# STM32F767ZI_eval_1.net
KiCad netlist of a schematic drawn in EAGLE
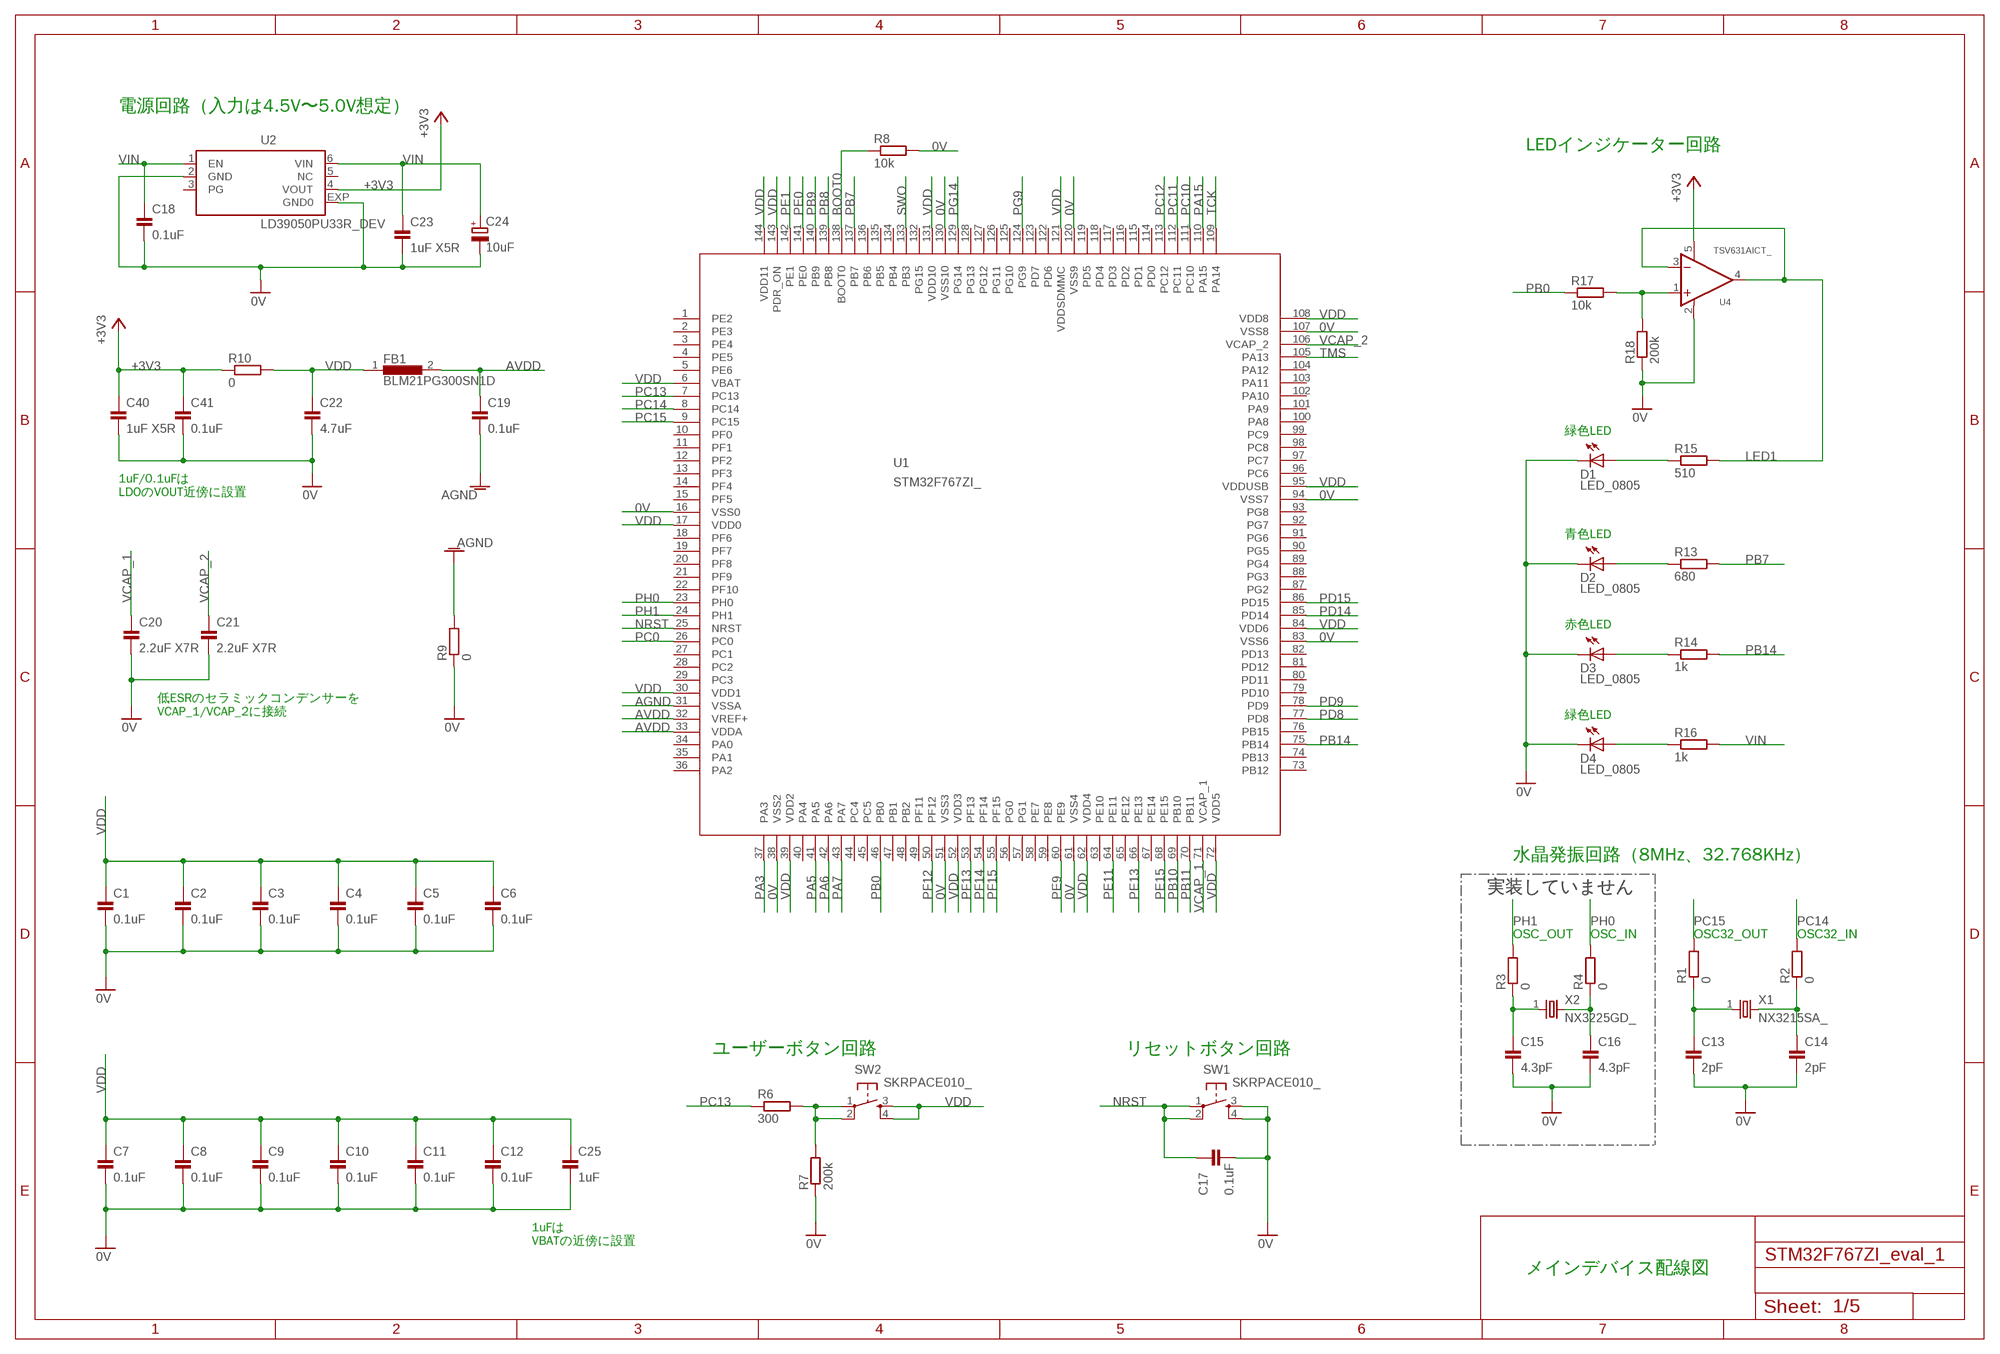
[diagram p0: schematic, sheet 1]
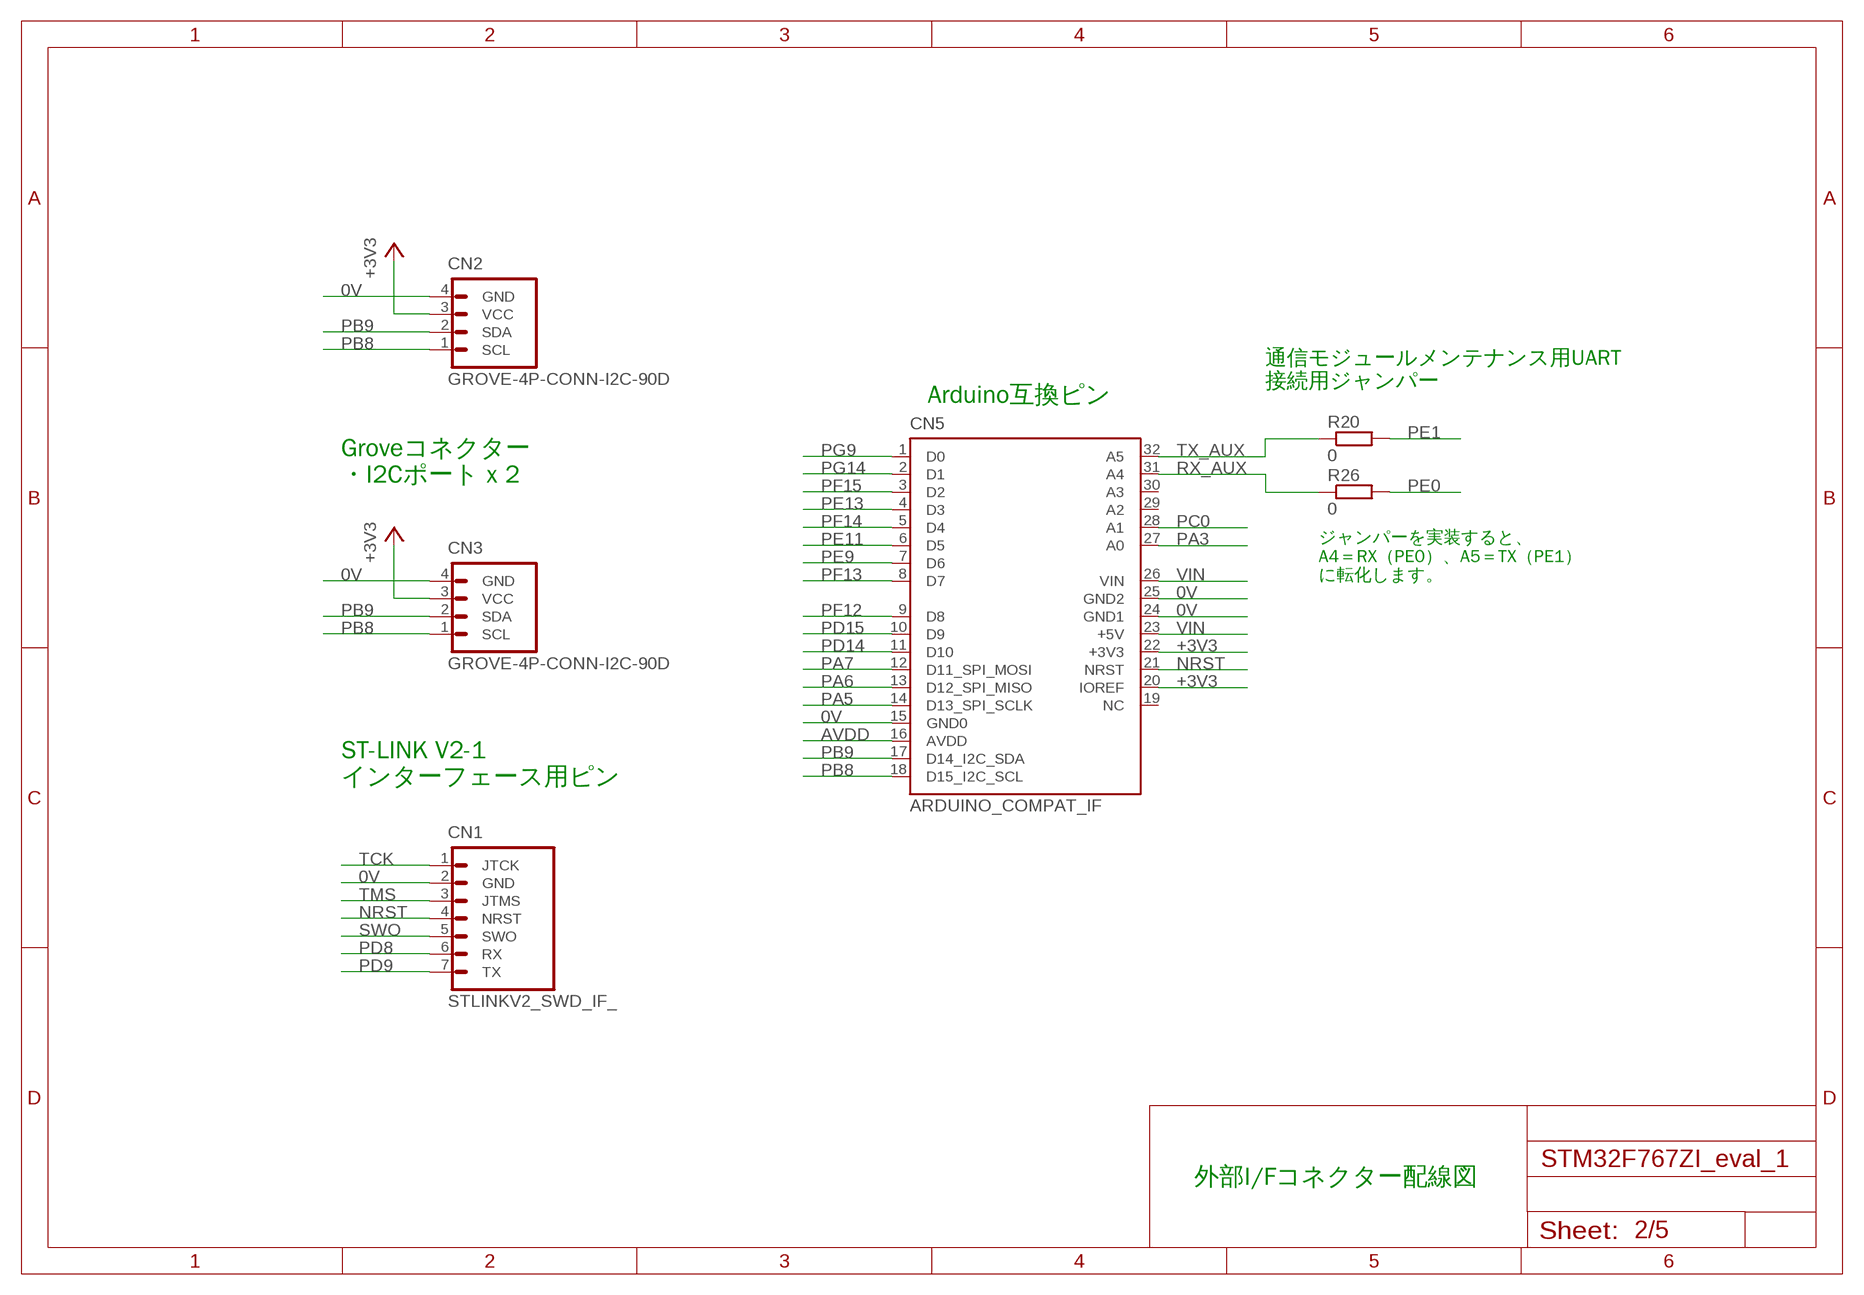
[diagram p1: schematic, sheet 2]
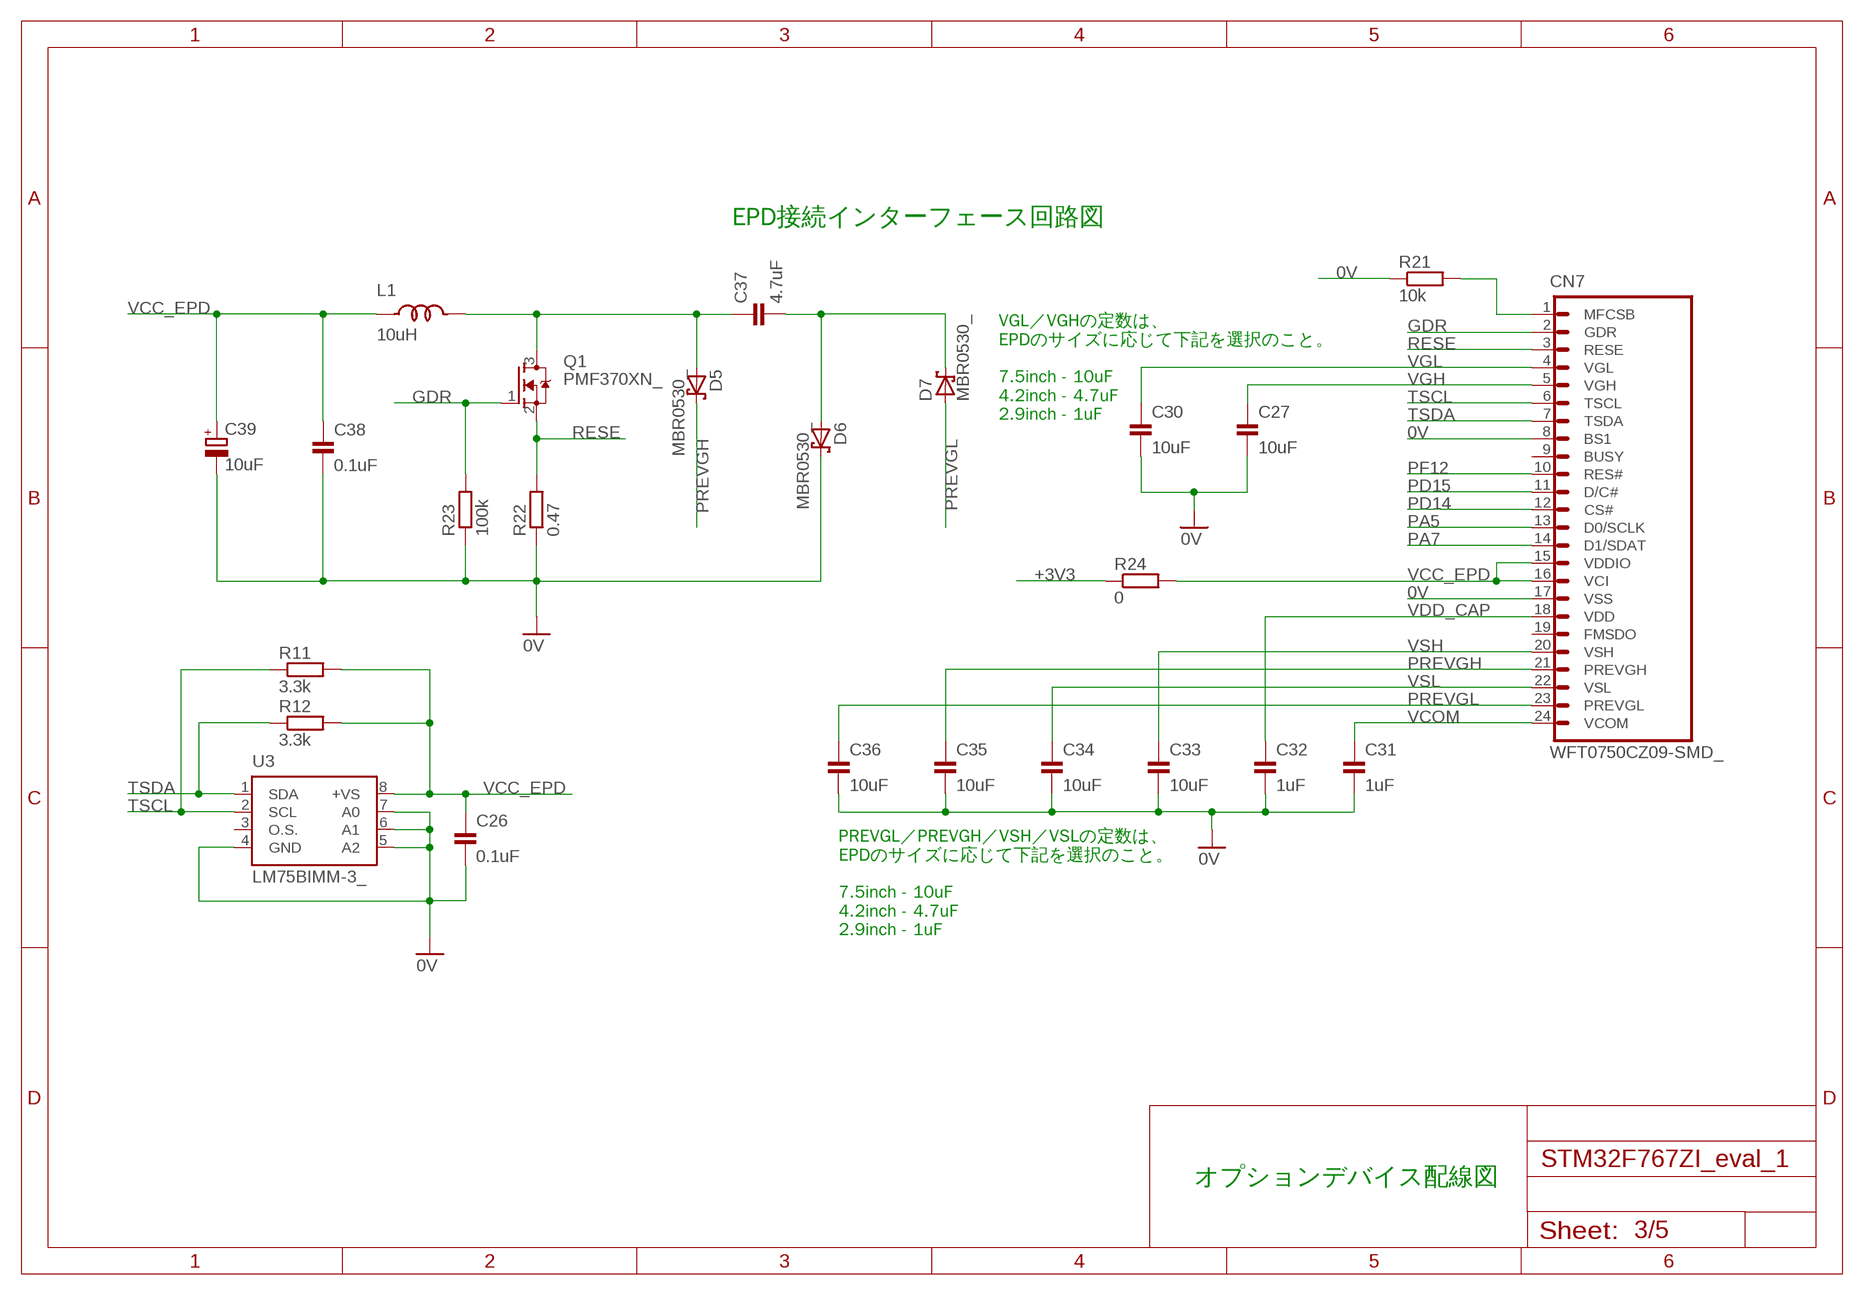
[diagram p2: schematic, sheet 3]
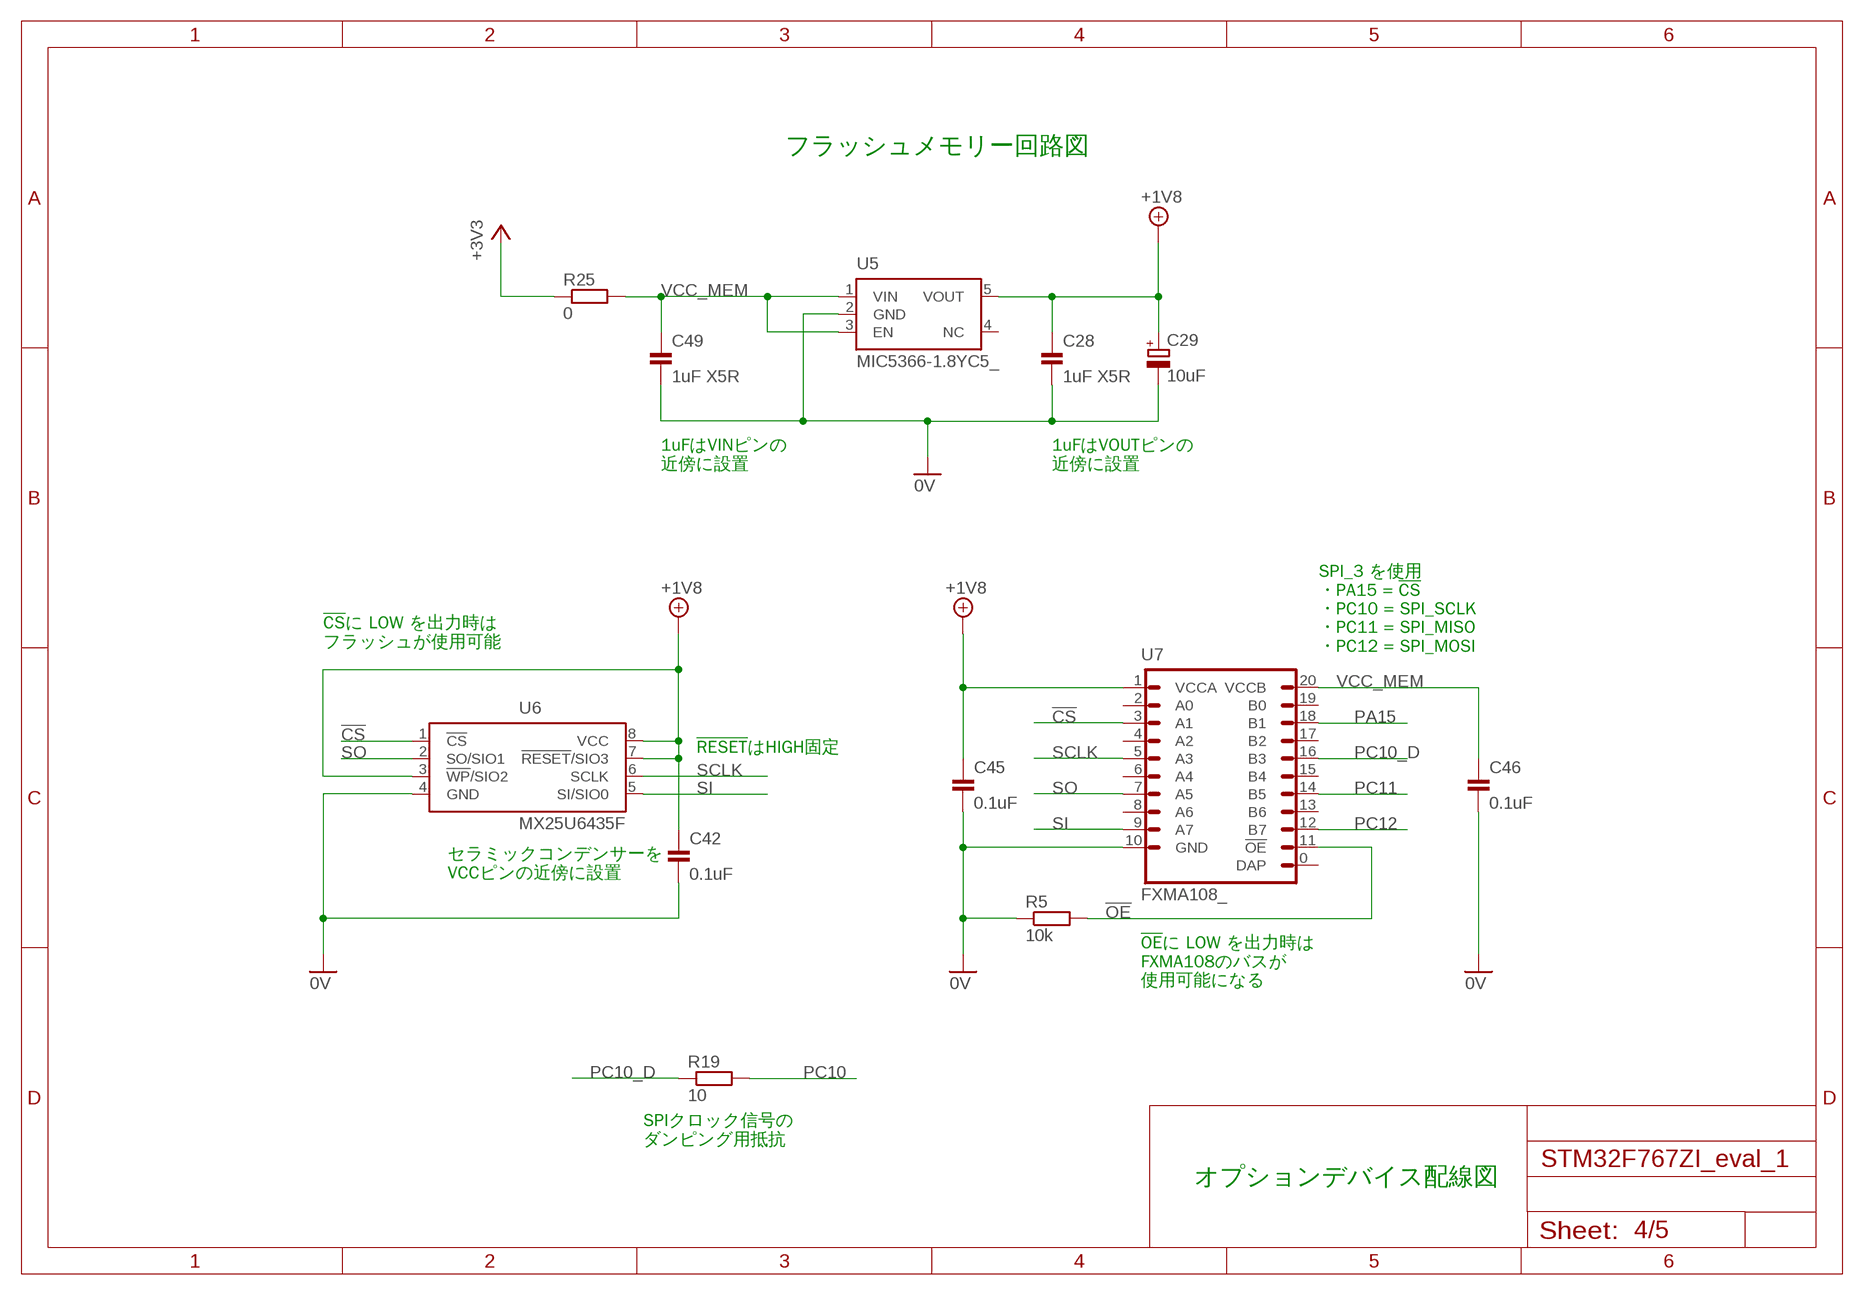
[diagram p3: schematic, sheet 4]
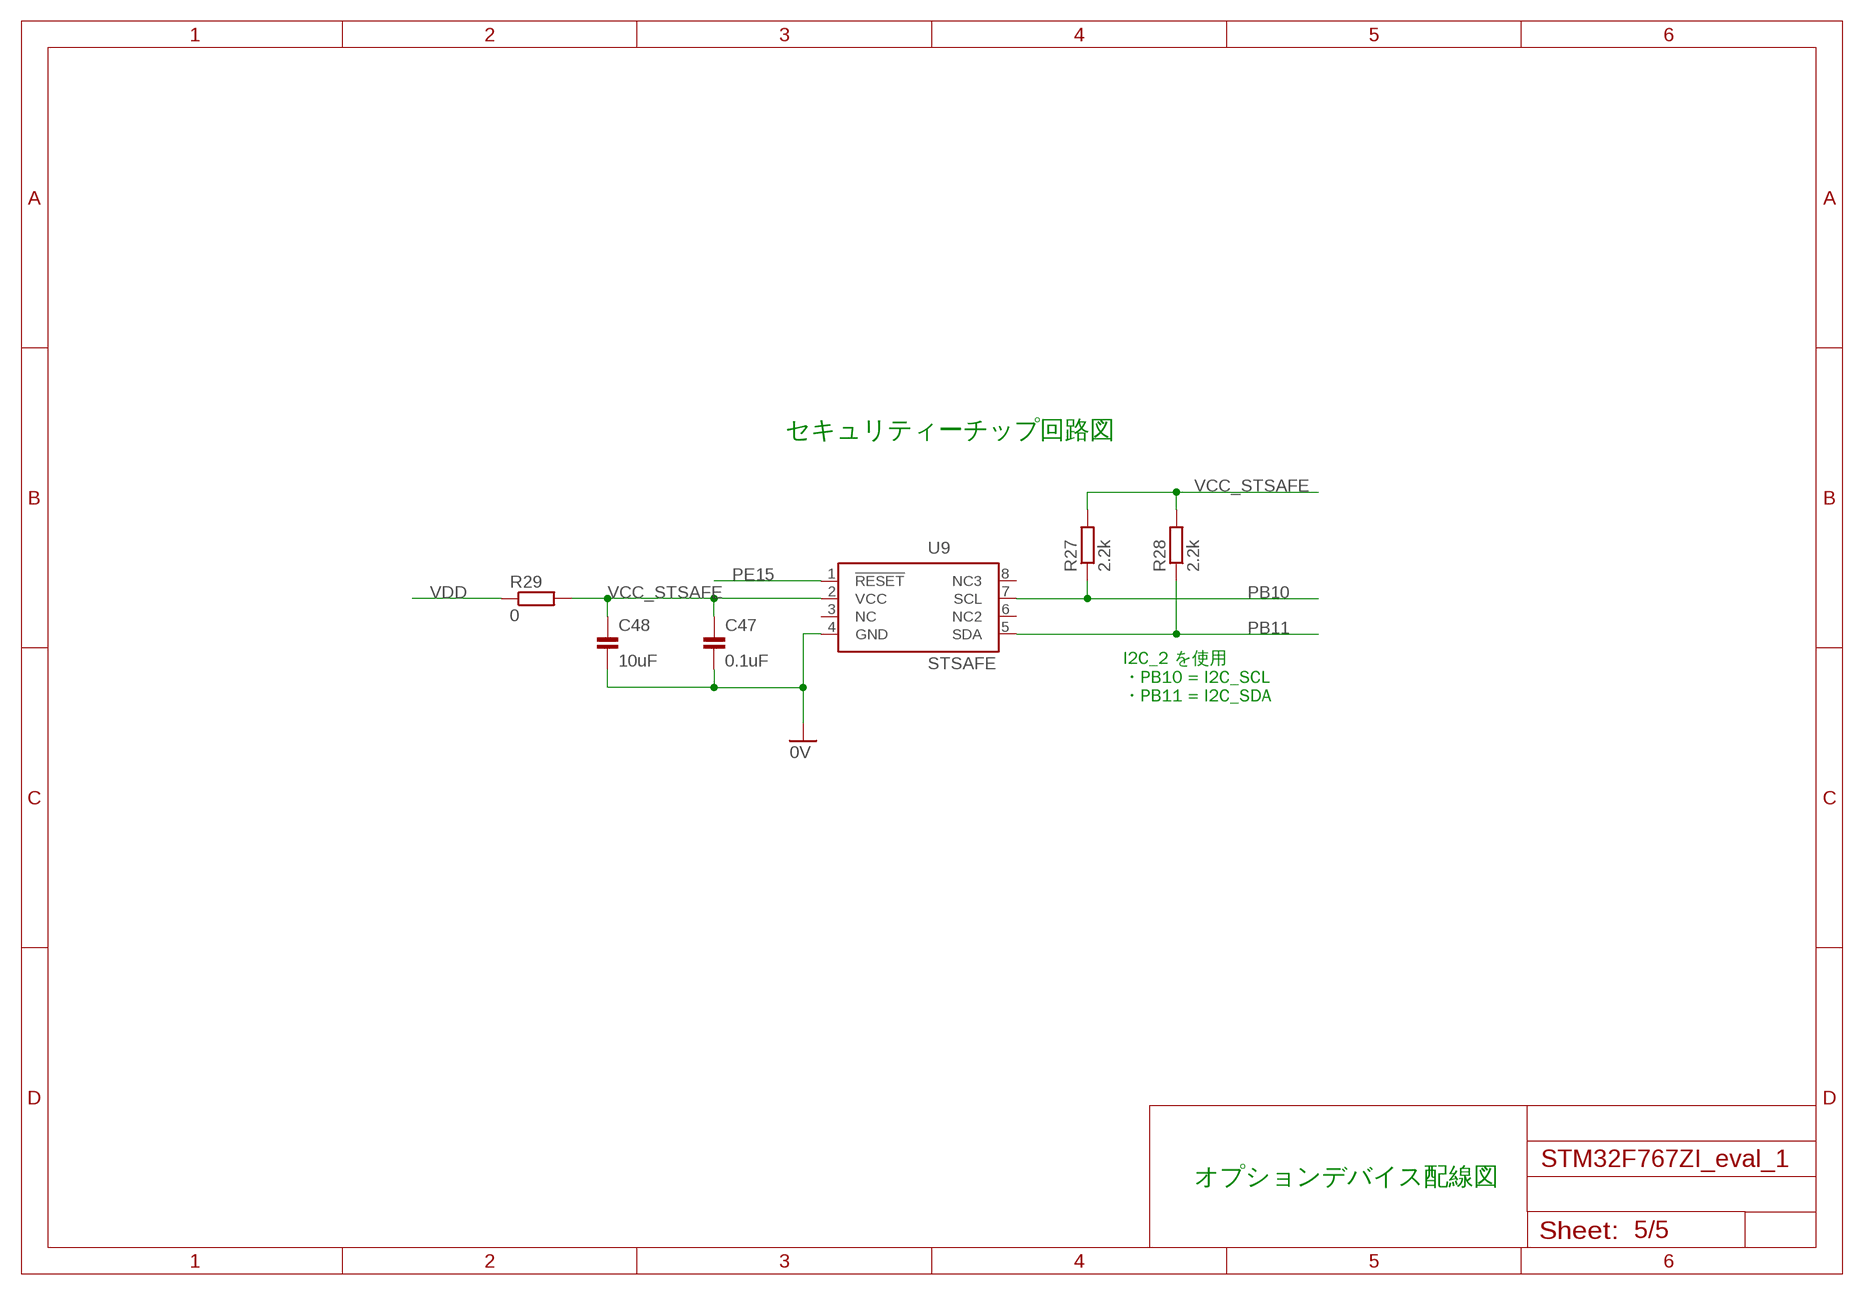
[diagram p4: schematic, sheet 5]

(export (version "E")
  (design (tool "Eeschema 10.0.6"))
  (components
    (comp (ref "C1")
      (value "0.1uF")
      (footprint "eagle-import:SMD_1608_DEV")
      (libsource (lib "eagle-import") (part "CAP_0603_DEV"))
    )
    (comp (ref "C2")
      (value "0.1uF")
      (footprint "eagle-import:SMD_1608_DEV")
      (libsource (lib "eagle-import") (part "CAP_0603_DEV"))
    )
    (comp (ref "C3")
      (value "0.1uF")
      (footprint "eagle-import:SMD_1608_DEV")
      (libsource (lib "eagle-import") (part "CAP_0603_DEV"))
    )
    (comp (ref "C4")
      (value "0.1uF")
      (footprint "eagle-import:SMD_1608_DEV")
      (libsource (lib "eagle-import") (part "CAP_0603_DEV"))
    )
    (comp (ref "C5")
      (value "0.1uF")
      (footprint "eagle-import:SMD_1608_DEV")
      (libsource (lib "eagle-import") (part "CAP_0603_DEV"))
    )
    (comp (ref "C6")
      (value "0.1uF")
      (footprint "eagle-import:SMD_1608_DEV")
      (libsource (lib "eagle-import") (part "CAP_0603_DEV"))
    )
    (comp (ref "C7")
      (value "0.1uF")
      (footprint "eagle-import:SMD_1608_DEV")
      (libsource (lib "eagle-import") (part "CAP_0603_DEV"))
    )
    (comp (ref "C8")
      (value "0.1uF")
      (footprint "eagle-import:SMD_1608_DEV")
      (libsource (lib "eagle-import") (part "CAP_0603_DEV"))
    )
    (comp (ref "C9")
      (value "0.1uF")
      (footprint "eagle-import:SMD_1608_DEV")
      (libsource (lib "eagle-import") (part "CAP_0603_DEV"))
    )
    (comp (ref "C10")
      (value "0.1uF")
      (footprint "eagle-import:SMD_1608_DEV")
      (libsource (lib "eagle-import") (part "CAP_0603_DEV"))
    )
    (comp (ref "C11")
      (value "0.1uF")
      (footprint "eagle-import:SMD_1608_DEV")
      (libsource (lib "eagle-import") (part "CAP_0603_DEV"))
    )
    (comp (ref "C12")
      (value "0.1uF")
      (footprint "eagle-import:SMD_1608_DEV")
      (libsource (lib "eagle-import") (part "CAP_0603_DEV"))
    )
    (comp (ref "C13")
      (value "2pF")
      (footprint "eagle-import:SMD_1608_DEV")
      (libsource (lib "eagle-import") (part "CAP_0603_DEV"))
    )
    (comp (ref "C14")
      (value "2pF")
      (footprint "eagle-import:SMD_1608_DEV")
      (libsource (lib "eagle-import") (part "CAP_0603_DEV"))
    )
    (comp (ref "C15")
      (value "4.3pF")
      (footprint "eagle-import:SMD_1608_DEV")
      (libsource (lib "eagle-import") (part "CAP_0603_DEV"))
    )
    (comp (ref "C16")
      (value "4.3pF")
      (footprint "eagle-import:SMD_1608_DEV")
      (libsource (lib "eagle-import") (part "CAP_0603_DEV"))
    )
    (comp (ref "C17")
      (value "0.1uF")
      (footprint "eagle-import:SMD_1608_DEV")
      (libsource (lib "eagle-import") (part "CAP_0603_DEV"))
    )
    (comp (ref "C18")
      (value "0.1uF")
      (footprint "eagle-import:SMD_1608_DEV")
      (libsource (lib "eagle-import") (part "CAP_0603_DEV"))
    )
    (comp (ref "C19")
      (value "0.1uF")
      (footprint "eagle-import:SMD_1608_DEV")
      (libsource (lib "eagle-import") (part "CAP_0603_DEV"))
    )
    (comp (ref "C20")
      (value "2.2uF X7R")
      (footprint "eagle-import:C1206")
      (libsource (lib "eagle-import") (part "CAP_1206"))
    )
    (comp (ref "C21")
      (value "2.2uF X7R")
      (footprint "eagle-import:C1206")
      (libsource (lib "eagle-import") (part "CAP_1206"))
    )
    (comp (ref "C22")
      (value "4.7uF")
      (footprint "eagle-import:SMD_2012_DEV")
      (libsource (lib "eagle-import") (part "CAP_0805_DEV"))
    )
    (comp (ref "C23")
      (value "1uF X5R")
      (footprint "eagle-import:SMD_1608_DEV")
      (libsource (lib "eagle-import") (part "CAP_0603_DEV"))
    )
    (comp (ref "C24")
      (value "10uF")
      (footprint "eagle-import:C1210_TPST_DEV")
      (libsource (lib "eagle-import") (part "TPST106K016R0800_"))
    )
    (comp (ref "C25")
      (value "1uF")
      (footprint "eagle-import:SMD_1608_DEV")
      (libsource (lib "eagle-import") (part "CAP_0603_DEV"))
    )
    (comp (ref "C40")
      (value "1uF X5R")
      (footprint "eagle-import:SMD_1608_DEV")
      (libsource (lib "eagle-import") (part "CAP_0603_DEV"))
    )
    (comp (ref "C41")
      (value "0.1uF")
      (footprint "eagle-import:SMD_1608_DEV")
      (libsource (lib "eagle-import") (part "CAP_0603_DEV"))
    )
    (comp (ref "D1")
      (value "LED_0805")
      (footprint "eagle-import:CHIPLED_0805")
      (libsource (lib "eagle-import") (part "LED_0805"))
    )
    (comp (ref "D2")
      (value "LED_0805")
      (footprint "eagle-import:CHIPLED_0805")
      (libsource (lib "eagle-import") (part "LED_0805"))
    )
    (comp (ref "D3")
      (value "LED_0805")
      (footprint "eagle-import:CHIPLED_0805")
      (libsource (lib "eagle-import") (part "LED_0805"))
    )
    (comp (ref "D4")
      (value "LED_0805")
      (footprint "eagle-import:CHIPLED_0805")
      (libsource (lib "eagle-import") (part "LED_0805"))
    )
    (comp (ref "FB1")
      (value "BLM21PG300SN1D")
      (footprint "eagle-import:SMD_2012_DEV")
      (libsource (lib "eagle-import") (part "BLM21PG300SN1D"))
    )
    (comp (ref "R1")
      (value "0")
      (footprint "eagle-import:SMD_1608_DEV")
      (libsource (lib "eagle-import") (part "RESISTOR_0603_DEV"))
    )
    (comp (ref "R2")
      (value "0")
      (footprint "eagle-import:SMD_1608_DEV")
      (libsource (lib "eagle-import") (part "RESISTOR_0603_DEV"))
    )
    (comp (ref "R3")
      (value "0")
      (footprint "eagle-import:SMD_1608_DEV")
      (libsource (lib "eagle-import") (part "RESISTOR_0603_DEV"))
    )
    (comp (ref "R4")
      (value "0")
      (footprint "eagle-import:SMD_1608_DEV")
      (libsource (lib "eagle-import") (part "RESISTOR_0603_DEV"))
    )
    (comp (ref "R6")
      (value "300")
      (footprint "eagle-import:SMD_1608_DEV")
      (libsource (lib "eagle-import") (part "RESISTOR_0603_DEV"))
    )
    (comp (ref "R7")
      (value "200k")
      (footprint "eagle-import:SMD_1608_DEV")
      (libsource (lib "eagle-import") (part "RESISTOR_0603_DEV"))
    )
    (comp (ref "R8")
      (value "10k")
      (footprint "eagle-import:SMD_1608_DEV")
      (libsource (lib "eagle-import") (part "RESISTOR_0603_DEV"))
    )
    (comp (ref "R9")
      (value "0")
      (footprint "eagle-import:SMD_1608_DEV")
      (libsource (lib "eagle-import") (part "RESISTOR_0603_DEV"))
    )
    (comp (ref "R10")
      (value "0")
      (footprint "eagle-import:SMD_1608_DEV")
      (libsource (lib "eagle-import") (part "RESISTOR_0603_DEV"))
    )
    (comp (ref "R13")
      (value "680")
      (footprint "eagle-import:SMD_1608_DEV")
      (libsource (lib "eagle-import") (part "RESISTOR_0603_DEV"))
    )
    (comp (ref "R14")
      (value "1k")
      (footprint "eagle-import:SMD_1608_DEV")
      (libsource (lib "eagle-import") (part "RESISTOR_0603_DEV"))
    )
    (comp (ref "R15")
      (value "510")
      (footprint "eagle-import:SMD_1608_DEV")
      (libsource (lib "eagle-import") (part "RESISTOR_0603_DEV"))
    )
    (comp (ref "R16")
      (value "1k")
      (footprint "eagle-import:SMD_1608_DEV")
      (libsource (lib "eagle-import") (part "RESISTOR_0603_DEV"))
    )
    (comp (ref "R17")
      (value "10k")
      (footprint "eagle-import:SMD_1608_DEV")
      (libsource (lib "eagle-import") (part "RESISTOR_0603_DEV"))
    )
    (comp (ref "R18")
      (value "200k")
      (footprint "eagle-import:SMD_1608_DEV")
      (libsource (lib "eagle-import") (part "RESISTOR_0603_DEV"))
    )
    (comp (ref "SW1")
      (value "SKRPACE010_")
      (footprint "eagle-import:SKRPACE010_DEV")
      (libsource (lib "eagle-import") (part "SKRPACE010_"))
    )
    (comp (ref "SW2")
      (value "SKRPACE010_")
      (footprint "eagle-import:SKRPACE010_DEV")
      (libsource (lib "eagle-import") (part "SKRPACE010_"))
    )
    (comp (ref "U1")
      (value "STM32F767ZI_")
      (footprint "eagle-import:LQFP144_DEV")
      (libsource (lib "eagle-import") (part "STM32F767ZI_"))
    )
    (comp (ref "U2")
      (value "LD39050PU33R_DEV")
      (footprint "eagle-import:DFN6-3X3_")
      (libsource (lib "eagle-import") (part "LD39050PU33R_DEV"))
    )
    (comp (ref "U4")
      (value "TSV631AICT_")
      (footprint "eagle-import:SC-70-5_DEV")
      (libsource (lib "eagle-import") (part "TSV631AICT_"))
    )
    (comp (ref "X1")
      (value "NX3215SA_")
      (footprint "eagle-import:NX3215_DEV")
      (libsource (lib "eagle-import") (part "NX3215SA_"))
    )
    (comp (ref "X2")
      (value "NX3225GD_")
      (footprint "eagle-import:NX3225_DEV")
      (libsource (lib "eagle-import") (part "NX3225GD_"))
    )
    (comp (ref "C47")
      (value "0.1uF")
      (footprint "eagle-import:SMD_1608_DEV")
      (libsource (lib "eagle-import") (part "CAP_0603_DEV"))
    )
    (comp (ref "C48")
      (value "10uF")
      (footprint "eagle-import:SMD_2012_DEV")
      (libsource (lib "eagle-import") (part "CAP_0805_DEV"))
    )
    (comp (ref "R27")
      (value "2.2k")
      (footprint "eagle-import:SMD_1608_DEV")
      (libsource (lib "eagle-import") (part "RESISTOR_0603_DEV"))
    )
    (comp (ref "R28")
      (value "2.2k")
      (footprint "eagle-import:SMD_1608_DEV")
      (libsource (lib "eagle-import") (part "RESISTOR_0603_DEV"))
    )
    (comp (ref "R29")
      (value "0")
      (footprint "eagle-import:SMD_1608_DEV")
      (libsource (lib "eagle-import") (part "RESISTOR_0603_DEV"))
    )
    (comp (ref "U9")
      (value "STSAFE")
      (footprint "eagle-import:SO8N")
      (libsource (lib "eagle-import") (part "STSAFE"))
    )
    (comp (ref "C26")
      (value "0.1uF")
      (footprint "eagle-import:SMD_1608_DEV")
      (libsource (lib "eagle-import") (part "CAP_0603_DEV"))
    )
    (comp (ref "C27")
      (value "10uF")
      (footprint "eagle-import:SMD_2012_DEV")
      (libsource (lib "eagle-import") (part "CAP_0805_DEV"))
    )
    (comp (ref "C30")
      (value "10uF")
      (footprint "eagle-import:SMD_2012_DEV")
      (libsource (lib "eagle-import") (part "CAP_0805_DEV"))
    )
    (comp (ref "C31")
      (value "1uF")
      (footprint "eagle-import:SMD_2012_DEV")
      (libsource (lib "eagle-import") (part "CAP_0805_DEV"))
    )
    (comp (ref "C32")
      (value "1uF")
      (footprint "eagle-import:SMD_2012_DEV")
      (libsource (lib "eagle-import") (part "CAP_0805_DEV"))
    )
    (comp (ref "C33")
      (value "10uF")
      (footprint "eagle-import:SMD_2012_DEV")
      (libsource (lib "eagle-import") (part "CAP_0805_DEV"))
    )
    (comp (ref "C34")
      (value "10uF")
      (footprint "eagle-import:SMD_2012_DEV")
      (libsource (lib "eagle-import") (part "CAP_0805_DEV"))
    )
    (comp (ref "C35")
      (value "10uF")
      (footprint "eagle-import:SMD_2012_DEV")
      (libsource (lib "eagle-import") (part "CAP_0805_DEV"))
    )
    (comp (ref "C36")
      (value "10uF")
      (footprint "eagle-import:SMD_2012_DEV")
      (libsource (lib "eagle-import") (part "CAP_0805_DEV"))
    )
    (comp (ref "C37")
      (value "4.7uF")
      (footprint "eagle-import:SMD_2012_DEV")
      (libsource (lib "eagle-import") (part "CAP_0805_DEV"))
    )
    (comp (ref "C38")
      (value "0.1uF")
      (footprint "eagle-import:SMD_1608_DEV")
      (libsource (lib "eagle-import") (part "CAP_0603_DEV"))
    )
    (comp (ref "C39")
      (value "10uF")
      (footprint "eagle-import:C1210_TPST_DEV")
      (libsource (lib "eagle-import") (part "TPST106K016R0800_"))
    )
    (comp (ref "CN7")
      (value "WFT0750CZ09-SMD_")
      (footprint "eagle-import:FH12A-24S-0.5SH_DEV")
      (libsource (lib "eagle-import") (part "WFT0750CZ09-SMD_"))
    )
    (comp (ref "D5")
      (value "MBR0530_")
      (footprint "eagle-import:MBR0530_DEV")
      (libsource (lib "eagle-import") (part "MBR0530_"))
    )
    (comp (ref "D6")
      (value "MBR0530_")
      (footprint "eagle-import:MBR0530_DEV")
      (libsource (lib "eagle-import") (part "MBR0530_"))
    )
    (comp (ref "D7")
      (value "MBR0530_")
      (footprint "eagle-import:MBR0530_DEV")
      (libsource (lib "eagle-import") (part "MBR0530_"))
    )
    (comp (ref "L1")
      (value "10uH")
      (footprint "eagle-import:NLCV25T_DEV")
      (libsource (lib "eagle-import") (part "NLCV25T_"))
    )
    (comp (ref "Q1")
      (value "PMF370XN_")
      (footprint "eagle-import:SOT323_DEV")
      (libsource (lib "eagle-import") (part "PMF370XN_"))
    )
    (comp (ref "R11")
      (value "3.3k")
      (footprint "eagle-import:SMD_2012_DEV")
      (libsource (lib "eagle-import") (part "RESISTOR_0805_DEV"))
    )
    (comp (ref "R12")
      (value "3.3k")
      (footprint "eagle-import:SMD_2012_DEV")
      (libsource (lib "eagle-import") (part "RESISTOR_0805_DEV"))
    )
    (comp (ref "R21")
      (value "10k")
      (footprint "eagle-import:SMD_1608_DEV")
      (libsource (lib "eagle-import") (part "RESISTOR_0603_DEV"))
    )
    (comp (ref "R22")
      (value "0.47")
      (footprint "eagle-import:SMD_2012_DEV")
      (libsource (lib "eagle-import") (part "RESISTOR_0805_DEV"))
    )
    (comp (ref "R23")
      (value "100k")
      (footprint "eagle-import:SMD_2012_DEV")
      (libsource (lib "eagle-import") (part "RESISTOR_0805_DEV"))
    )
    (comp (ref "R24")
      (value "0")
      (footprint "eagle-import:SMD_1608_DEV")
      (libsource (lib "eagle-import") (part "RESISTOR_0603_DEV"))
    )
    (comp (ref "U3")
      (value "LM75BIMM-3_")
      (footprint "eagle-import:SSOP8-DGK_DEV")
      (libsource (lib "eagle-import") (part "LM75BIMM-3_"))
    )
    (comp (ref "C28")
      (value "1uF X5R")
      (footprint "eagle-import:SMD_1608_DEV")
      (libsource (lib "eagle-import") (part "CAP_0603_DEV"))
    )
    (comp (ref "C29")
      (value "10uF")
      (footprint "eagle-import:C1210_TPST_DEV")
      (libsource (lib "eagle-import") (part "TPST106K016R0800_"))
    )
    (comp (ref "C42")
      (value "0.1uF")
      (footprint "eagle-import:SMD_1608_DEV")
      (libsource (lib "eagle-import") (part "CAP_0603_DEV"))
    )
    (comp (ref "C45")
      (value "0.1uF")
      (footprint "eagle-import:SMD_1608_DEV")
      (libsource (lib "eagle-import") (part "CAP_0603_DEV"))
    )
    (comp (ref "C46")
      (value "0.1uF")
      (footprint "eagle-import:SMD_1608_DEV")
      (libsource (lib "eagle-import") (part "CAP_0603_DEV"))
    )
    (comp (ref "C49")
      (value "1uF X5R")
      (footprint "eagle-import:SMD_1608_DEV")
      (libsource (lib "eagle-import") (part "CAP_0603_DEV"))
    )
    (comp (ref "R5")
      (value "10k")
      (footprint "eagle-import:SMD_1608_DEV")
      (libsource (lib "eagle-import") (part "RESISTOR_0603_DEV"))
    )
    (comp (ref "R19")
      (value "10")
      (footprint "eagle-import:SMD_1608_DEV")
      (libsource (lib "eagle-import") (part "RESISTOR_0603_DEV"))
    )
    (comp (ref "R25")
      (value "0")
      (footprint "eagle-import:SMD_1608_DEV")
      (libsource (lib "eagle-import") (part "RESISTOR_0603_DEV"))
    )
    (comp (ref "U5")
      (value "MIC5366-1.8YC5_")
      (footprint "eagle-import:SC-70-5_DEV")
      (libsource (lib "eagle-import") (part "MIC5366-1.8YC5_"))
    )
    (comp (ref "U6")
      (value "MX25U6435F")
      (footprint "eagle-import:SOP_8L")
      (libsource (lib "eagle-import") (part "MX25U6435F"))
    )
    (comp (ref "U7")
      (value "FXMA108_")
      (footprint "eagle-import:DQFN20_DEV")
      (libsource (lib "eagle-import") (part "FXMA108_"))
    )
    (comp (ref "CN1")
      (value "STLINKV2_SWD_IF_")
      (footprint "eagle-import:DF65-7P-1.7V_DEV")
      (libsource (lib "eagle-import") (part "STLINKV2_SWD_IF_"))
    )
    (comp (ref "CN2")
      (value "GROVE-4P-CONN-I2C-90D")
      (footprint "eagle-import:GROVE-4P-90D")
      (libsource (lib "eagle-import") (part "GROVE-4P-CONN-I2C-90D"))
    )
    (comp (ref "CN3")
      (value "GROVE-4P-CONN-I2C-90D")
      (footprint "eagle-import:GROVE-4P-90D")
      (libsource (lib "eagle-import") (part "GROVE-4P-CONN-I2C-90D"))
    )
    (comp (ref "CN5")
      (value "ARDUINO_COMPAT_IF")
      (footprint "eagle-import:ARDUINO_COMPAT_IF")
      (libsource (lib "eagle-import") (part "ARDUINO_COMPAT_IF"))
    )
    (comp (ref "R20")
      (value "0")
      (footprint "eagle-import:SMD_1608_DEV")
      (libsource (lib "eagle-import") (part "RESISTOR_0603_DEV"))
    )
    (comp (ref "R26")
      (value "0")
      (footprint "eagle-import:SMD_1608_DEV")
      (libsource (lib "eagle-import") (part "RESISTOR_0603_DEV"))
    )
  )
  (nets
    (net (code "1") (name "+1V8") (class "Default")
      (node (ref "C28") (pin "1") (pinfunction "1_1") (pintype "passive"))
      (node (ref "C29") (pin "1") (pinfunction "+_1") (pintype "passive"))
      (node (ref "C42") (pin "1") (pinfunction "1_1") (pintype "passive"))
      (node (ref "C45") (pin "1") (pinfunction "1_1") (pintype "passive"))
      (node (ref "U5") (pin "5") (pinfunction "VOUT_5") (pintype "passive"))
      (node (ref "U6") (pin "3") (pinfunction "~{WP}/SIO2_3") (pintype "bidirectional"))
      (node (ref "U6") (pin "7") (pinfunction "~{RESET}/SIO3_7") (pintype "bidirectional"))
      (node (ref "U6") (pin "8") (pinfunction "VCC_8") (pintype "passive"))
      (node (ref "U7") (pin "1") (pinfunction "VCCA_1") (pintype "passive"))
    )
    (net (code "2") (name "+3V3") (class "Default")
      (node (ref "C40") (pin "1") (pinfunction "1_1") (pintype "passive"))
      (node (ref "C41") (pin "1") (pinfunction "1_1") (pintype "passive"))
      (node (ref "CN2") (pin "3") (pinfunction "VCC_3") (pintype "passive"))
      (node (ref "CN3") (pin "3") (pinfunction "VCC_3") (pintype "passive"))
      (node (ref "CN5") (pin "20") (pinfunction "IOREF_20") (pintype "bidirectional"))
      (node (ref "CN5") (pin "22") (pinfunction "+3V3_22") (pintype "passive"))
      (node (ref "R10") (pin "1") (pinfunction "1_1") (pintype "passive"))
      (node (ref "R24") (pin "1") (pinfunction "1_1") (pintype "passive"))
      (node (ref "R25") (pin "1") (pinfunction "1_1") (pintype "passive"))
      (node (ref "U2") (pin "4") (pinfunction "VOUT_4") (pintype "passive"))
      (node (ref "U4") (pin "5") (pinfunction "V+_5") (pintype "passive"))
    )
    (net (code "3") (name "0V") (class "Default")
      (node (ref "C1") (pin "2") (pinfunction "2_2") (pintype "passive"))
      (node (ref "C10") (pin "2") (pinfunction "2_2") (pintype "passive"))
      (node (ref "C11") (pin "2") (pinfunction "2_2") (pintype "passive"))
      (node (ref "C12") (pin "2") (pinfunction "2_2") (pintype "passive"))
      (node (ref "C13") (pin "2") (pinfunction "2_2") (pintype "passive"))
      (node (ref "C14") (pin "2") (pinfunction "2_2") (pintype "passive"))
      (node (ref "C15") (pin "2") (pinfunction "2_2") (pintype "passive"))
      (node (ref "C16") (pin "2") (pinfunction "2_2") (pintype "passive"))
      (node (ref "C17") (pin "2") (pinfunction "2_2") (pintype "passive"))
      (node (ref "C18") (pin "2") (pinfunction "2_2") (pintype "passive"))
      (node (ref "C2") (pin "2") (pinfunction "2_2") (pintype "passive"))
      (node (ref "C20") (pin "2") (pinfunction "2_2") (pintype "passive"))
      (node (ref "C21") (pin "2") (pinfunction "2_2") (pintype "passive"))
      (node (ref "C22") (pin "2") (pinfunction "2_2") (pintype "passive"))
      (node (ref "C23") (pin "2") (pinfunction "2_2") (pintype "passive"))
      (node (ref "C24") (pin "2") (pinfunction "-_2") (pintype "passive"))
      (node (ref "C25") (pin "2") (pinfunction "2_2") (pintype "passive"))
      (node (ref "C26") (pin "2") (pinfunction "2_2") (pintype "passive"))
      (node (ref "C27") (pin "2") (pinfunction "2_2") (pintype "passive"))
      (node (ref "C28") (pin "2") (pinfunction "2_2") (pintype "passive"))
      (node (ref "C29") (pin "2") (pinfunction "-_2") (pintype "passive"))
      (node (ref "C3") (pin "2") (pinfunction "2_2") (pintype "passive"))
      (node (ref "C30") (pin "2") (pinfunction "2_2") (pintype "passive"))
      (node (ref "C31") (pin "2") (pinfunction "2_2") (pintype "passive"))
      (node (ref "C32") (pin "2") (pinfunction "2_2") (pintype "passive"))
      (node (ref "C33") (pin "2") (pinfunction "2_2") (pintype "passive"))
      (node (ref "C34") (pin "2") (pinfunction "2_2") (pintype "passive"))
      (node (ref "C35") (pin "2") (pinfunction "2_2") (pintype "passive"))
      (node (ref "C36") (pin "2") (pinfunction "2_2") (pintype "passive"))
      (node (ref "C38") (pin "2") (pinfunction "2_2") (pintype "passive"))
      (node (ref "C39") (pin "2") (pinfunction "-_2") (pintype "passive"))
      (node (ref "C4") (pin "2") (pinfunction "2_2") (pintype "passive"))
      (node (ref "C40") (pin "2") (pinfunction "2_2") (pintype "passive"))
      (node (ref "C41") (pin "2") (pinfunction "2_2") (pintype "passive"))
      (node (ref "C42") (pin "2") (pinfunction "2_2") (pintype "passive"))
      (node (ref "C45") (pin "2") (pinfunction "2_2") (pintype "passive"))
      (node (ref "C46") (pin "2") (pinfunction "2_2") (pintype "passive"))
      (node (ref "C47") (pin "2") (pinfunction "2_2") (pintype "passive"))
      (node (ref "C48") (pin "2") (pinfunction "2_2") (pintype "passive"))
      (node (ref "C49") (pin "2") (pinfunction "2_2") (pintype "passive"))
      (node (ref "C5") (pin "2") (pinfunction "2_2") (pintype "passive"))
      (node (ref "C6") (pin "2") (pinfunction "2_2") (pintype "passive"))
      (node (ref "C7") (pin "2") (pinfunction "2_2") (pintype "passive"))
      (node (ref "C8") (pin "2") (pinfunction "2_2") (pintype "passive"))
      (node (ref "C9") (pin "2") (pinfunction "2_2") (pintype "passive"))
      (node (ref "CN1") (pin "2") (pinfunction "GND_2") (pintype "passive"))
      (node (ref "CN2") (pin "4") (pinfunction "GND_4") (pintype "passive"))
      (node (ref "CN3") (pin "4") (pinfunction "GND_4") (pintype "passive"))
      (node (ref "CN5") (pin "15") (pinfunction "GND0_15") (pintype "passive"))
      (node (ref "CN5") (pin "24") (pinfunction "GND1_24") (pintype "passive"))
      (node (ref "CN5") (pin "25") (pinfunction "GND2_25") (pintype "passive"))
      (node (ref "CN7") (pin "17") (pinfunction "VSS_17") (pintype "passive"))
      (node (ref "CN7") (pin "8") (pinfunction "BS1_8") (pintype "input"))
      (node (ref "D1") (pin "C") (pinfunction "C_C") (pintype "passive"))
      (node (ref "D2") (pin "C") (pinfunction "C_C") (pintype "passive"))
      (node (ref "D3") (pin "C") (pinfunction "C_C") (pintype "passive"))
      (node (ref "D4") (pin "C") (pinfunction "C_C") (pintype "passive"))
      (node (ref "D6") (pin "1") (pinfunction "C_1") (pintype "passive"))
      (node (ref "R18") (pin "1") (pinfunction "1_1") (pintype "passive"))
      (node (ref "R21") (pin "1") (pinfunction "1_1") (pintype "passive"))
      (node (ref "R22") (pin "1") (pinfunction "1_1") (pintype "passive"))
      (node (ref "R23") (pin "1") (pinfunction "1_1") (pintype "passive"))
      (node (ref "R5") (pin "1") (pinfunction "1_1") (pintype "passive"))
      (node (ref "R7") (pin "1") (pinfunction "1_1") (pintype "passive"))
      (node (ref "R8") (pin "2") (pinfunction "2_2") (pintype "passive"))
      (node (ref "R9") (pin "1") (pinfunction "1_1") (pintype "passive"))
      (node (ref "SW1") (pin "3") (pinfunction "S_3") (pintype "passive"))
      (node (ref "SW1") (pin "4") (pinfunction "S1_4") (pintype "passive"))
      (node (ref "U1") (pin "107") (pinfunction "VSS8_107") (pintype "passive"))
      (node (ref "U1") (pin "120") (pinfunction "VSS9_120") (pintype "passive"))
      (node (ref "U1") (pin "130") (pinfunction "VSS10_130") (pintype "passive"))
      (node (ref "U1") (pin "16") (pinfunction "VSS0_16") (pintype "passive"))
      (node (ref "U1") (pin "38") (pinfunction "VSS2_38") (pintype "passive"))
      (node (ref "U1") (pin "51") (pinfunction "VSS3_51") (pintype "bidirectional"))
      (node (ref "U1") (pin "61") (pinfunction "VSS4_61") (pintype "passive"))
      (node (ref "U1") (pin "83") (pinfunction "VSS6_83") (pintype "passive"))
      (node (ref "U1") (pin "94") (pinfunction "VSS7_94") (pintype "passive"))
      (node (ref "U2") (pin "2") (pinfunction "GND_2") (pintype "passive"))
      (node (ref "U2") (pin "EXP") (pinfunction "GND0_EXP") (pintype "passive"))
      (node (ref "U3") (pin "4") (pinfunction "GND_4") (pintype "passive"))
      (node (ref "U3") (pin "5") (pinfunction "A2_5") (pintype "bidirectional"))
      (node (ref "U3") (pin "6") (pinfunction "A1_6") (pintype "bidirectional"))
      (node (ref "U3") (pin "7") (pinfunction "A0_7") (pintype "bidirectional"))
      (node (ref "U4") (pin "2") (pinfunction "V-_2") (pintype "passive"))
      (node (ref "U5") (pin "2") (pinfunction "GND_2") (pintype "passive"))
      (node (ref "U6") (pin "4") (pinfunction "GND_4") (pintype "passive"))
      (node (ref "U7") (pin "10") (pinfunction "GND_10") (pintype "passive"))
      (node (ref "U9") (pin "4") (pinfunction "GND_4") (pintype "passive"))
    )
    (net (code "4") (name "AGND") (class "Default")
      (node (ref "C19") (pin "2") (pinfunction "2_2") (pintype "passive"))
      (node (ref "R9") (pin "2") (pinfunction "2_2") (pintype "passive"))
      (node (ref "U1") (pin "31") (pinfunction "VSSA_31") (pintype "passive"))
    )
    (net (code "5") (name "AVDD") (class "Default")
      (node (ref "C19") (pin "1") (pinfunction "1_1") (pintype "passive"))
      (node (ref "CN5") (pin "16") (pinfunction "AVDD_16") (pintype "passive"))
      (node (ref "FB1") (pin "2") (pinfunction "2_2") (pintype "passive"))
      (node (ref "U1") (pin "32") (pinfunction "VREF+_32") (pintype "passive"))
      (node (ref "U1") (pin "33") (pinfunction "VDDA_33") (pintype "passive"))
    )
    (net (code "6") (name "BOOT0") (class "Default")
      (node (ref "R8") (pin "1") (pinfunction "1_1") (pintype "passive"))
      (node (ref "U1") (pin "138") (pinfunction "BOOT0_138") (pintype "bidirectional"))
    )
    (net (code "7") (name "GDR") (class "Default")
      (node (ref "CN7") (pin "2") (pinfunction "GDR_2") (pintype "output"))
      (node (ref "Q1") (pin "1") (pinfunction "G_1") (pintype "passive"))
      (node (ref "R23") (pin "2") (pinfunction "2_2") (pintype "passive"))
    )
    (net (code "8") (name "LED1") (class "Default")
      (node (ref "R15") (pin "2") (pinfunction "2_2") (pintype "passive"))
      (node (ref "U4") (pin "3") (pinfunction "IN-_3") (pintype "input"))
      (node (ref "U4") (pin "4") (pinfunction "OUT_4") (pintype "output"))
    )
    (net (code "9") (name "NRST") (class "Default")
      (node (ref "C17") (pin "1") (pinfunction "1_1") (pintype "passive"))
      (node (ref "CN1") (pin "4") (pinfunction "NRST_4") (pintype "bidirectional"))
      (node (ref "CN5") (pin "21") (pinfunction "NRST_21") (pintype "bidirectional"))
      (node (ref "SW1") (pin "1") (pinfunction "P_1") (pintype "passive"))
      (node (ref "SW1") (pin "2") (pinfunction "P1_2") (pintype "passive"))
      (node (ref "U1") (pin "25") (pinfunction "NRST_25") (pintype "bidirectional"))
    )
    (net (code "10") (name "Net-(C13-Pad1)") (class "Default")
      (node (ref "C13") (pin "1") (pinfunction "1_1") (pintype "passive"))
      (node (ref "R1") (pin "1") (pinfunction "1_1") (pintype "passive"))
      (node (ref "X1") (pin "1") (pinfunction "1_1") (pintype "passive"))
    )
    (net (code "11") (name "Net-(C14-Pad1)") (class "Default")
      (node (ref "C14") (pin "1") (pinfunction "1_1") (pintype "passive"))
      (node (ref "R2") (pin "1") (pinfunction "1_1") (pintype "passive"))
      (node (ref "X1") (pin "2") (pinfunction "2_2") (pintype "passive"))
    )
    (net (code "12") (name "Net-(C15-Pad1)") (class "Default")
      (node (ref "C15") (pin "1") (pinfunction "1_1") (pintype "passive"))
      (node (ref "R3") (pin "1") (pinfunction "1_1") (pintype "passive"))
      (node (ref "X2") (pin "1") (pinfunction "1_1") (pintype "passive"))
    )
    (net (code "13") (name "Net-(C16-Pad1)") (class "Default")
      (node (ref "C16") (pin "1") (pinfunction "1_1") (pintype "passive"))
      (node (ref "R4") (pin "1") (pinfunction "1_1") (pintype "passive"))
      (node (ref "X2") (pin "2") (pinfunction "2_2") (pintype "passive"))
    )
    (net (code "14") (name "Net-(CN7-MFCSB)") (class "Default")
      (node (ref "CN7") (pin "1") (pinfunction "MFCSB_1") (pintype "input"))
      (node (ref "R21") (pin "2") (pinfunction "2_2") (pintype "passive"))
    )
    (net (code "15") (name "Net-(D1-PadA)") (class "Default")
      (node (ref "D1") (pin "A") (pinfunction "A_A") (pintype "passive"))
      (node (ref "R15") (pin "1") (pinfunction "1_1") (pintype "passive"))
    )
    (net (code "16") (name "Net-(D2-PadA)") (class "Default")
      (node (ref "D2") (pin "A") (pinfunction "A_A") (pintype "passive"))
      (node (ref "R13") (pin "1") (pinfunction "1_1") (pintype "passive"))
    )
    (net (code "17") (name "Net-(D3-PadA)") (class "Default")
      (node (ref "D3") (pin "A") (pinfunction "A_A") (pintype "passive"))
      (node (ref "R14") (pin "1") (pinfunction "1_1") (pintype "passive"))
    )
    (net (code "18") (name "Net-(D4-PadA)") (class "Default")
      (node (ref "D4") (pin "A") (pinfunction "A_A") (pintype "passive"))
      (node (ref "R16") (pin "1") (pinfunction "1_1") (pintype "passive"))
    )
    (net (code "19") (name "Net-(D5-A)") (class "Default")
      (node (ref "C37") (pin "1") (pinfunction "1_1") (pintype "passive"))
      (node (ref "D5") (pin "2") (pinfunction "A_2") (pintype "passive"))
      (node (ref "L1") (pin "2") (pinfunction "2_2") (pintype "passive"))
      (node (ref "Q1") (pin "3") (pinfunction "D_3") (pintype "passive"))
    )
    (net (code "20") (name "Net-(D6-A)") (class "Default")
      (node (ref "C37") (pin "2") (pinfunction "2_2") (pintype "passive"))
      (node (ref "D6") (pin "2") (pinfunction "A_2") (pintype "passive"))
      (node (ref "D7") (pin "1") (pinfunction "C_1") (pintype "passive"))
    )
    (net (code "21") (name "Net-(SW2-P)") (class "Default")
      (node (ref "R6") (pin "2") (pinfunction "2_2") (pintype "passive"))
      (node (ref "R7") (pin "2") (pinfunction "2_2") (pintype "passive"))
      (node (ref "SW2") (pin "1") (pinfunction "P_1") (pintype "passive"))
      (node (ref "SW2") (pin "2") (pinfunction "P1_2") (pintype "passive"))
    )
    (net (code "22") (name "Net-(U4-IN+)") (class "Default")
      (node (ref "R17") (pin "2") (pinfunction "2_2") (pintype "passive"))
      (node (ref "R18") (pin "2") (pinfunction "2_2") (pintype "passive"))
      (node (ref "U4") (pin "1") (pinfunction "IN+_1") (pintype "input"))
    )
    (net (code "23") (name "PA3") (class "Default")
      (node (ref "CN5") (pin "27") (pinfunction "A0_27") (pintype "bidirectional"))
      (node (ref "U1") (pin "37") (pinfunction "PA3_37") (pintype "bidirectional"))
    )
    (net (code "24") (name "PA5") (class "Default")
      (node (ref "CN5") (pin "14") (pinfunction "D13_SPI_SCLK_14") (pintype "bidirectional"))
      (node (ref "CN7") (pin "13") (pinfunction "D0/SCLK_13") (pintype "bidirectional"))
      (node (ref "U1") (pin "41") (pinfunction "PA5_41") (pintype "bidirectional"))
    )
    (net (code "25") (name "PA6") (class "Default")
      (node (ref "CN5") (pin "13") (pinfunction "D12_SPI_MISO_13") (pintype "bidirectional"))
      (node (ref "U1") (pin "42") (pinfunction "PA6_42") (pintype "bidirectional"))
    )
    (net (code "26") (name "PA7") (class "Default")
      (node (ref "CN5") (pin "12") (pinfunction "D11_SPI_MOSI_12") (pintype "bidirectional"))
      (node (ref "CN7") (pin "14") (pinfunction "D1/SDAT_14") (pintype "bidirectional"))
      (node (ref "U1") (pin "43") (pinfunction "PA7_43") (pintype "bidirectional"))
    )
    (net (code "27") (name "PA15") (class "Default")
      (node (ref "U1") (pin "110") (pinfunction "PA15_110") (pintype "bidirectional"))
      (node (ref "U7") (pin "18") (pinfunction "B1_18") (pintype "bidirectional"))
    )
    (net (code "28") (name "PB0") (class "Default")
      (node (ref "R17") (pin "1") (pinfunction "1_1") (pintype "passive"))
      (node (ref "U1") (pin "46") (pinfunction "PB0_46") (pintype "bidirectional"))
    )
    (net (code "29") (name "PB7") (class "Default")
      (node (ref "R13") (pin "2") (pinfunction "2_2") (pintype "passive"))
      (node (ref "U1") (pin "137") (pinfunction "PB7_137") (pintype "bidirectional"))
    )
    (net (code "30") (name "PB8") (class "Default")
      (node (ref "CN2") (pin "1") (pinfunction "SCL_1") (pintype "bidirectional"))
      (node (ref "CN3") (pin "1") (pinfunction "SCL_1") (pintype "bidirectional"))
      (node (ref "CN5") (pin "18") (pinfunction "D15_I2C_SCL_18") (pintype "passive"))
      (node (ref "U1") (pin "139") (pinfunction "PB8_139") (pintype "bidirectional"))
    )
    (net (code "31") (name "PB9") (class "Default")
      (node (ref "CN2") (pin "2") (pinfunction "SDA_2") (pintype "bidirectional"))
      (node (ref "CN3") (pin "2") (pinfunction "SDA_2") (pintype "bidirectional"))
      (node (ref "CN5") (pin "17") (pinfunction "D14_I2C_SDA_17") (pintype "passive"))
      (node (ref "U1") (pin "140") (pinfunction "PB9_140") (pintype "bidirectional"))
    )
    (net (code "32") (name "PB10") (class "Default")
      (node (ref "R27") (pin "1") (pinfunction "1_1") (pintype "passive"))
      (node (ref "U1") (pin "69") (pinfunction "PB10_69") (pintype "bidirectional"))
      (node (ref "U9") (pin "7") (pinfunction "SCL_7") (pintype "bidirectional"))
    )
    (net (code "33") (name "PB11") (class "Default")
      (node (ref "R28") (pin "1") (pinfunction "1_1") (pintype "passive"))
      (node (ref "U1") (pin "70") (pinfunction "PB11_70") (pintype "bidirectional"))
      (node (ref "U9") (pin "5") (pinfunction "SDA_5") (pintype "bidirectional"))
    )
    (net (code "34") (name "PB14") (class "Default")
      (node (ref "R14") (pin "2") (pinfunction "2_2") (pintype "passive"))
      (node (ref "U1") (pin "75") (pinfunction "PB14_75") (pintype "bidirectional"))
    )
    (net (code "35") (name "PC0") (class "Default")
      (node (ref "CN5") (pin "28") (pinfunction "A1_28") (pintype "bidirectional"))
      (node (ref "U1") (pin "26") (pinfunction "PC0_26") (pintype "bidirectional"))
    )
    (net (code "36") (name "PC10") (class "Default")
      (node (ref "R19") (pin "2") (pinfunction "2_2") (pintype "passive"))
      (node (ref "U1") (pin "111") (pinfunction "PC10_111") (pintype "bidirectional"))
    )
    (net (code "37") (name "PC10_D") (class "Default")
      (node (ref "R19") (pin "1") (pinfunction "1_1") (pintype "passive"))
      (node (ref "U7") (pin "16") (pinfunction "B3_16") (pintype "bidirectional"))
    )
    (net (code "38") (name "PC11") (class "Default")
      (node (ref "U1") (pin "112") (pinfunction "PC11_112") (pintype "bidirectional"))
      (node (ref "U7") (pin "14") (pinfunction "B5_14") (pintype "bidirectional"))
    )
    (net (code "39") (name "PC12") (class "Default")
      (node (ref "U1") (pin "113") (pinfunction "PC12_113") (pintype "bidirectional"))
      (node (ref "U7") (pin "12") (pinfunction "B7_12") (pintype "bidirectional"))
    )
    (net (code "40") (name "PC13") (class "Default")
      (node (ref "R6") (pin "1") (pinfunction "1_1") (pintype "passive"))
      (node (ref "U1") (pin "7") (pinfunction "PC13_7") (pintype "bidirectional"))
    )
    (net (code "41") (name "PC14") (class "Default")
      (node (ref "R2") (pin "2") (pinfunction "2_2") (pintype "passive"))
      (node (ref "U1") (pin "8") (pinfunction "PC14_8") (pintype "bidirectional"))
    )
    (net (code "42") (name "PC15") (class "Default")
      (node (ref "R1") (pin "2") (pinfunction "2_2") (pintype "passive"))
      (node (ref "U1") (pin "9") (pinfunction "PC15_9") (pintype "bidirectional"))
    )
    (net (code "43") (name "PD8") (class "Default")
      (node (ref "CN1") (pin "6") (pinfunction "RX_6") (pintype "bidirectional"))
      (node (ref "U1") (pin "77") (pinfunction "PD8_77") (pintype "bidirectional"))
    )
    (net (code "44") (name "PD9") (class "Default")
      (node (ref "CN1") (pin "7") (pinfunction "TX_7") (pintype "bidirectional"))
      (node (ref "U1") (pin "78") (pinfunction "PD9_78") (pintype "bidirectional"))
    )
    (net (code "45") (name "PD14") (class "Default")
      (node (ref "CN5") (pin "11") (pinfunction "D10_11") (pintype "bidirectional"))
      (node (ref "CN7") (pin "12") (pinfunction "CS#_12") (pintype "input"))
      (node (ref "U1") (pin "85") (pinfunction "PD14_85") (pintype "bidirectional"))
    )
    (net (code "46") (name "PD15") (class "Default")
      (node (ref "CN5") (pin "10") (pinfunction "D9_10") (pintype "bidirectional"))
      (node (ref "CN7") (pin "11") (pinfunction "D/C#_11") (pintype "input"))
      (node (ref "U1") (pin "86") (pinfunction "PD15_86") (pintype "bidirectional"))
    )
    (net (code "47") (name "PE0") (class "Default")
      (node (ref "R26") (pin "2") (pinfunction "2_2") (pintype "passive"))
      (node (ref "U1") (pin "141") (pinfunction "PE0_141") (pintype "bidirectional"))
    )
    (net (code "48") (name "PE1") (class "Default")
      (node (ref "R20") (pin "2") (pinfunction "2_2") (pintype "passive"))
      (node (ref "U1") (pin "142") (pinfunction "PE1_142") (pintype "bidirectional"))
    )
    (net (code "49") (name "PE9") (class "Default")
      (node (ref "CN5") (pin "7") (pinfunction "D6_7") (pintype "bidirectional"))
      (node (ref "U1") (pin "60") (pinfunction "PE9_60") (pintype "bidirectional"))
    )
    (net (code "50") (name "PE11") (class "Default")
      (node (ref "CN5") (pin "6") (pinfunction "D5_6") (pintype "bidirectional"))
      (node (ref "U1") (pin "64") (pinfunction "PE11_64") (pintype "bidirectional"))
    )
    (net (code "51") (name "PE13") (class "Default")
      (node (ref "CN5") (pin "4") (pinfunction "D3_4") (pintype "bidirectional"))
      (node (ref "U1") (pin "66") (pinfunction "PE13_66") (pintype "bidirectional"))
    )
    (net (code "52") (name "PE15") (class "Default")
      (node (ref "U1") (pin "68") (pinfunction "PE15_68") (pintype "bidirectional"))
      (node (ref "U9") (pin "1") (pinfunction "~{RESET}_1") (pintype "bidirectional"))
    )
    (net (code "53") (name "PF12") (class "Default")
      (node (ref "CN5") (pin "9") (pinfunction "D8_9") (pintype "bidirectional"))
      (node (ref "CN7") (pin "10") (pinfunction "RES#_10") (pintype "input"))
      (node (ref "U1") (pin "50") (pinfunction "PF12_50") (pintype "bidirectional"))
    )
    (net (code "54") (name "PF13") (class "Default")
      (node (ref "CN5") (pin "8") (pinfunction "D7_8") (pintype "bidirectional"))
      (node (ref "U1") (pin "53") (pinfunction "PF13_53") (pintype "bidirectional"))
    )
    (net (code "55") (name "PF14") (class "Default")
      (node (ref "CN5") (pin "5") (pinfunction "D4_5") (pintype "bidirectional"))
      (node (ref "U1") (pin "54") (pinfunction "PF14_54") (pintype "bidirectional"))
    )
    (net (code "56") (name "PF15") (class "Default")
      (node (ref "CN5") (pin "3") (pinfunction "D2_3") (pintype "bidirectional"))
      (node (ref "U1") (pin "55") (pinfunction "PF15_55") (pintype "bidirectional"))
    )
    (net (code "57") (name "PG9") (class "Default")
      (node (ref "CN5") (pin "1") (pinfunction "D0_1") (pintype "bidirectional"))
      (node (ref "U1") (pin "124") (pinfunction "PG9_124") (pintype "bidirectional"))
    )
    (net (code "58") (name "PG14") (class "Default")
      (node (ref "CN5") (pin "2") (pinfunction "D1_2") (pintype "bidirectional"))
      (node (ref "U1") (pin "129") (pinfunction "PG14_129") (pintype "bidirectional"))
    )
    (net (code "59") (name "PH0") (class "Default")
      (node (ref "R4") (pin "2") (pinfunction "2_2") (pintype "passive"))
      (node (ref "U1") (pin "23") (pinfunction "PH0_23") (pintype "bidirectional"))
    )
    (net (code "60") (name "PH1") (class "Default")
      (node (ref "R3") (pin "2") (pinfunction "2_2") (pintype "passive"))
      (node (ref "U1") (pin "24") (pinfunction "PH1_24") (pintype "bidirectional"))
    )
    (net (code "61") (name "PREVGH") (class "Default")
      (node (ref "C35") (pin "1") (pinfunction "1_1") (pintype "passive"))
      (node (ref "CN7") (pin "21") (pinfunction "PREVGH_21") (pintype "passive"))
      (node (ref "D5") (pin "1") (pinfunction "C_1") (pintype "passive"))
    )
    (net (code "62") (name "PREVGL") (class "Default")
      (node (ref "C36") (pin "1") (pinfunction "1_1") (pintype "passive"))
      (node (ref "CN7") (pin "23") (pinfunction "PREVGL_23") (pintype "passive"))
      (node (ref "D7") (pin "2") (pinfunction "A_2") (pintype "passive"))
    )
    (net (code "63") (name "RESE") (class "Default")
      (node (ref "CN7") (pin "3") (pinfunction "RESE_3") (pintype "output"))
      (node (ref "Q1") (pin "2") (pinfunction "S_2") (pintype "passive"))
      (node (ref "R22") (pin "2") (pinfunction "2_2") (pintype "passive"))
    )
    (net (code "64") (name "RX_AUX") (class "Default")
      (node (ref "CN5") (pin "31") (pinfunction "A4_31") (pintype "bidirectional"))
      (node (ref "R26") (pin "1") (pinfunction "1_1") (pintype "passive"))
    )
    (net (code "65") (name "SCLK") (class "Default")
      (node (ref "U6") (pin "6") (pinfunction "SCLK_6") (pintype "bidirectional"))
      (node (ref "U7") (pin "5") (pinfunction "A3_5") (pintype "bidirectional"))
    )
    (net (code "66") (name "SI") (class "Default")
      (node (ref "U6") (pin "5") (pinfunction "SI/SIO0_5") (pintype "bidirectional"))
      (node (ref "U7") (pin "9") (pinfunction "A7_9") (pintype "bidirectional"))
    )
    (net (code "67") (name "SO") (class "Default")
      (node (ref "U6") (pin "2") (pinfunction "SO/SIO1_2") (pintype "bidirectional"))
      (node (ref "U7") (pin "7") (pinfunction "A5_7") (pintype "bidirectional"))
    )
    (net (code "68") (name "SWO") (class "Default")
      (node (ref "CN1") (pin "5") (pinfunction "SWO_5") (pintype "bidirectional"))
      (node (ref "U1") (pin "133") (pinfunction "PB3_133") (pintype "bidirectional"))
    )
    (net (code "69") (name "TCK") (class "Default")
      (node (ref "CN1") (pin "1") (pinfunction "JTCK_1") (pintype "bidirectional"))
      (node (ref "U1") (pin "109") (pinfunction "PA14_109") (pintype "bidirectional"))
    )
    (net (code "70") (name "TMS") (class "Default")
      (node (ref "CN1") (pin "3") (pinfunction "JTMS_3") (pintype "bidirectional"))
      (node (ref "U1") (pin "105") (pinfunction "PA13_105") (pintype "bidirectional"))
    )
    (net (code "71") (name "TSCL") (class "Default")
      (node (ref "CN7") (pin "6") (pinfunction "TSCL_6") (pintype "output"))
      (node (ref "R11") (pin "1") (pinfunction "1_1") (pintype "passive"))
      (node (ref "U3") (pin "2") (pinfunction "SCL_2") (pintype "bidirectional"))
    )
    (net (code "72") (name "TSDA") (class "Default")
      (node (ref "CN7") (pin "7") (pinfunction "TSDA_7") (pintype "bidirectional"))
      (node (ref "R12") (pin "1") (pinfunction "1_1") (pintype "passive"))
      (node (ref "U3") (pin "1") (pinfunction "SDA_1") (pintype "bidirectional"))
    )
    (net (code "73") (name "TX_AUX") (class "Default")
      (node (ref "CN5") (pin "32") (pinfunction "A5_32") (pintype "bidirectional"))
      (node (ref "R20") (pin "1") (pinfunction "1_1") (pintype "passive"))
    )
    (net (code "74") (name "VCAP_1") (class "Default")
      (node (ref "C20") (pin "1") (pinfunction "1_1") (pintype "passive"))
      (node (ref "U1") (pin "71") (pinfunction "VCAP_1_71") (pintype "passive"))
    )
    (net (code "75") (name "VCAP_2") (class "Default")
      (node (ref "C21") (pin "1") (pinfunction "1_1") (pintype "passive"))
      (node (ref "U1") (pin "106") (pinfunction "VCAP_2_106") (pintype "passive"))
    )
    (net (code "76") (name "VCC_EPD") (class "Default")
      (node (ref "C26") (pin "1") (pinfunction "1_1") (pintype "passive"))
      (node (ref "C38") (pin "1") (pinfunction "1_1") (pintype "passive"))
      (node (ref "C39") (pin "1") (pinfunction "+_1") (pintype "passive"))
      (node (ref "CN7") (pin "15") (pinfunction "VDDIO_15") (pintype "passive"))
      (node (ref "CN7") (pin "16") (pinfunction "VCI_16") (pintype "passive"))
      (node (ref "L1") (pin "1") (pinfunction "1_1") (pintype "passive"))
      (node (ref "R11") (pin "2") (pinfunction "2_2") (pintype "passive"))
      (node (ref "R12") (pin "2") (pinfunction "2_2") (pintype "passive"))
      (node (ref "R24") (pin "2") (pinfunction "2_2") (pintype "passive"))
      (node (ref "U3") (pin "8") (pinfunction "+VS_8") (pintype "passive"))
    )
    (net (code "77") (name "VCC_MEM") (class "Default")
      (node (ref "C46") (pin "1") (pinfunction "1_1") (pintype "passive"))
      (node (ref "C49") (pin "1") (pinfunction "1_1") (pintype "passive"))
      (node (ref "R25") (pin "2") (pinfunction "2_2") (pintype "passive"))
      (node (ref "U5") (pin "1") (pinfunction "VIN_1") (pintype "passive"))
      (node (ref "U5") (pin "3") (pinfunction "EN_3") (pintype "bidirectional"))
      (node (ref "U7") (pin "20") (pinfunction "VCCB_20") (pintype "passive"))
    )
    (net (code "78") (name "VCC_STSAFE") (class "Default")
      (node (ref "C47") (pin "1") (pinfunction "1_1") (pintype "passive"))
      (node (ref "C48") (pin "1") (pinfunction "1_1") (pintype "passive"))
      (node (ref "R27") (pin "2") (pinfunction "2_2") (pintype "passive"))
      (node (ref "R28") (pin "2") (pinfunction "2_2") (pintype "passive"))
      (node (ref "R29") (pin "2") (pinfunction "2_2") (pintype "passive"))
      (node (ref "U9") (pin "2") (pinfunction "VCC_2") (pintype "passive"))
    )
    (net (code "79") (name "VCOM") (class "Default")
      (node (ref "C31") (pin "1") (pinfunction "1_1") (pintype "passive"))
      (node (ref "CN7") (pin "24") (pinfunction "VCOM_24") (pintype "passive"))
    )
    (net (code "80") (name "VDD") (class "Default")
      (node (ref "C1") (pin "1") (pinfunction "1_1") (pintype "passive"))
      (node (ref "C10") (pin "1") (pinfunction "1_1") (pintype "passive"))
      (node (ref "C11") (pin "1") (pinfunction "1_1") (pintype "passive"))
      (node (ref "C12") (pin "1") (pinfunction "1_1") (pintype "passive"))
      (node (ref "C2") (pin "1") (pinfunction "1_1") (pintype "passive"))
      (node (ref "C22") (pin "1") (pinfunction "1_1") (pintype "passive"))
      (node (ref "C25") (pin "1") (pinfunction "1_1") (pintype "passive"))
      (node (ref "C3") (pin "1") (pinfunction "1_1") (pintype "passive"))
      (node (ref "C4") (pin "1") (pinfunction "1_1") (pintype "passive"))
      (node (ref "C5") (pin "1") (pinfunction "1_1") (pintype "passive"))
      (node (ref "C6") (pin "1") (pinfunction "1_1") (pintype "passive"))
      (node (ref "C7") (pin "1") (pinfunction "1_1") (pintype "passive"))
      (node (ref "C8") (pin "1") (pinfunction "1_1") (pintype "passive"))
      (node (ref "C9") (pin "1") (pinfunction "1_1") (pintype "passive"))
      (node (ref "FB1") (pin "1") (pinfunction "1_1") (pintype "passive"))
      (node (ref "R10") (pin "2") (pinfunction "2_2") (pintype "passive"))
      (node (ref "R29") (pin "1") (pinfunction "1_1") (pintype "passive"))
      (node (ref "SW2") (pin "3") (pinfunction "S_3") (pintype "passive"))
      (node (ref "SW2") (pin "4") (pinfunction "S1_4") (pintype "passive"))
      (node (ref "U1") (pin "108") (pinfunction "VDD8_108") (pintype "passive"))
      (node (ref "U1") (pin "121") (pinfunction "VDDSDMMC_121") (pintype "passive"))
      (node (ref "U1") (pin "131") (pinfunction "VDD10_131") (pintype "passive"))
      (node (ref "U1") (pin "143") (pinfunction "PDR_ON_143") (pintype "bidirectional"))
      (node (ref "U1") (pin "144") (pinfunction "VDD11_144") (pintype "passive"))
      (node (ref "U1") (pin "17") (pinfunction "VDD0_17") (pintype "passive"))
      (node (ref "U1") (pin "30") (pinfunction "VDD1_30") (pintype "passive"))
      (node (ref "U1") (pin "39") (pinfunction "VDD2_39") (pintype "passive"))
      (node (ref "U1") (pin "52") (pinfunction "VDD3_52") (pintype "passive"))
      (node (ref "U1") (pin "6") (pinfunction "VBAT_6") (pintype "passive"))
      (node (ref "U1") (pin "62") (pinfunction "VDD4_62") (pintype "passive"))
      (node (ref "U1") (pin "72") (pinfunction "VDD5_72") (pintype "passive"))
      (node (ref "U1") (pin "84") (pinfunction "VDD6_84") (pintype "passive"))
      (node (ref "U1") (pin "95") (pinfunction "VDDUSB_95") (pintype "passive"))
    )
    (net (code "81") (name "VDD_CAP") (class "Default")
      (node (ref "C32") (pin "1") (pinfunction "1_1") (pintype "passive"))
      (node (ref "CN7") (pin "18") (pinfunction "VDD_18") (pintype "passive"))
    )
    (net (code "82") (name "VGH") (class "Default")
      (node (ref "C27") (pin "1") (pinfunction "1_1") (pintype "passive"))
      (node (ref "CN7") (pin "5") (pinfunction "VGH_5") (pintype "passive"))
    )
    (net (code "83") (name "VGL") (class "Default")
      (node (ref "C30") (pin "1") (pinfunction "1_1") (pintype "passive"))
      (node (ref "CN7") (pin "4") (pinfunction "VGL_4") (pintype "passive"))
    )
    (net (code "84") (name "VIN") (class "Default")
      (node (ref "C18") (pin "1") (pinfunction "1_1") (pintype "passive"))
      (node (ref "C23") (pin "1") (pinfunction "1_1") (pintype "passive"))
      (node (ref "C24") (pin "1") (pinfunction "+_1") (pintype "passive"))
      (node (ref "CN5") (pin "23") (pinfunction "+5V_23") (pintype "passive"))
      (node (ref "CN5") (pin "26") (pinfunction "VIN_26") (pintype "passive"))
      (node (ref "R16") (pin "2") (pinfunction "2_2") (pintype "passive"))
      (node (ref "U2") (pin "1") (pinfunction "EN_1") (pintype "bidirectional"))
      (node (ref "U2") (pin "6") (pinfunction "VIN_6") (pintype "passive"))
    )
    (net (code "85") (name "VSH") (class "Default")
      (node (ref "C33") (pin "1") (pinfunction "1_1") (pintype "passive"))
      (node (ref "CN7") (pin "20") (pinfunction "VSH_20") (pintype "passive"))
    )
    (net (code "86") (name "VSL") (class "Default")
      (node (ref "C34") (pin "1") (pinfunction "1_1") (pintype "passive"))
      (node (ref "CN7") (pin "22") (pinfunction "VSL_22") (pintype "passive"))
    )
    (net (code "87") (name "unconnected-(CN5-A2-Pad29)") (class "Default")
      (node (ref "CN5") (pin "29") (pinfunction "A2_29") (pintype "bidirectional"))
    )
    (net (code "88") (name "unconnected-(CN5-A3-Pad30)") (class "Default")
      (node (ref "CN5") (pin "30") (pinfunction "A3_30") (pintype "bidirectional"))
    )
    (net (code "89") (name "unconnected-(CN5-NC-Pad19)") (class "Default")
      (node (ref "CN5") (pin "19") (pinfunction "NC_19") (pintype "no_connect"))
    )
    (net (code "90") (name "unconnected-(CN7-BUSY-Pad9)") (class "Default")
      (node (ref "CN7") (pin "9") (pinfunction "BUSY_9") (pintype "output"))
    )
    (net (code "91") (name "unconnected-(CN7-FMSDO-Pad19)") (class "Default")
      (node (ref "CN7") (pin "19") (pinfunction "FMSDO_19") (pintype "output"))
    )
    (net (code "92") (name "unconnected-(U1-PA0-Pad34)") (class "Default")
      (node (ref "U1") (pin "34") (pinfunction "PA0_34") (pintype "bidirectional"))
    )
    (net (code "93") (name "unconnected-(U1-PA1-Pad35)") (class "Default")
      (node (ref "U1") (pin "35") (pinfunction "PA1_35") (pintype "bidirectional"))
    )
    (net (code "94") (name "unconnected-(U1-PA2-Pad36)") (class "Default")
      (node (ref "U1") (pin "36") (pinfunction "PA2_36") (pintype "bidirectional"))
    )
    (net (code "95") (name "unconnected-(U1-PA4-Pad40)") (class "Default")
      (node (ref "U1") (pin "40") (pinfunction "PA4_40") (pintype "bidirectional"))
    )
    (net (code "96") (name "unconnected-(U1-PA8-Pad100)") (class "Default")
      (node (ref "U1") (pin "100") (pinfunction "PA8_100") (pintype "passive"))
    )
    (net (code "97") (name "unconnected-(U1-PA9-Pad101)") (class "Default")
      (node (ref "U1") (pin "101") (pinfunction "PA9_101") (pintype "passive"))
    )
    (net (code "98") (name "unconnected-(U1-PA10-Pad102)") (class "Default")
      (node (ref "U1") (pin "102") (pinfunction "PA10_102") (pintype "bidirectional"))
    )
    (net (code "99") (name "unconnected-(U1-PA11-Pad103)") (class "Default")
      (node (ref "U1") (pin "103") (pinfunction "PA11_103") (pintype "bidirectional"))
    )
    (net (code "100") (name "unconnected-(U1-PA12-Pad104)") (class "Default")
      (node (ref "U1") (pin "104") (pinfunction "PA12_104") (pintype "bidirectional"))
    )
    (net (code "101") (name "unconnected-(U1-PB1-Pad47)") (class "Default")
      (node (ref "U1") (pin "47") (pinfunction "PB1_47") (pintype "bidirectional"))
    )
    (net (code "102") (name "unconnected-(U1-PB2-Pad48)") (class "Default")
      (node (ref "U1") (pin "48") (pinfunction "PB2_48") (pintype "bidirectional"))
    )
    (net (code "103") (name "unconnected-(U1-PB4-Pad134)") (class "Default")
      (node (ref "U1") (pin "134") (pinfunction "PB4_134") (pintype "bidirectional"))
    )
    (net (code "104") (name "unconnected-(U1-PB5-Pad135)") (class "Default")
      (node (ref "U1") (pin "135") (pinfunction "PB5_135") (pintype "bidirectional"))
    )
    (net (code "105") (name "unconnected-(U1-PB6-Pad136)") (class "Default")
      (node (ref "U1") (pin "136") (pinfunction "PB6_136") (pintype "bidirectional"))
    )
    (net (code "106") (name "unconnected-(U1-PB12-Pad73)") (class "Default")
      (node (ref "U1") (pin "73") (pinfunction "PB12_73") (pintype "bidirectional"))
    )
    (net (code "107") (name "unconnected-(U1-PB13-Pad74)") (class "Default")
      (node (ref "U1") (pin "74") (pinfunction "PB13_74") (pintype "bidirectional"))
    )
    (net (code "108") (name "unconnected-(U1-PB15-Pad76)") (class "Default")
      (node (ref "U1") (pin "76") (pinfunction "PB15_76") (pintype "bidirectional"))
    )
    (net (code "109") (name "unconnected-(U1-PC1-Pad27)") (class "Default")
      (node (ref "U1") (pin "27") (pinfunction "PC1_27") (pintype "bidirectional"))
    )
    (net (code "110") (name "unconnected-(U1-PC2-Pad28)") (class "Default")
      (node (ref "U1") (pin "28") (pinfunction "PC2_28") (pintype "bidirectional"))
    )
    (net (code "111") (name "unconnected-(U1-PC3-Pad29)") (class "Default")
      (node (ref "U1") (pin "29") (pinfunction "PC3_29") (pintype "bidirectional"))
    )
    (net (code "112") (name "unconnected-(U1-PC4-Pad44)") (class "Default")
      (node (ref "U1") (pin "44") (pinfunction "PC4_44") (pintype "bidirectional"))
    )
    (net (code "113") (name "unconnected-(U1-PC5-Pad45)") (class "Default")
      (node (ref "U1") (pin "45") (pinfunction "PC5_45") (pintype "bidirectional"))
    )
    (net (code "114") (name "unconnected-(U1-PC6-Pad96)") (class "Default")
      (node (ref "U1") (pin "96") (pinfunction "PC6_96") (pintype "bidirectional"))
    )
    (net (code "115") (name "unconnected-(U1-PC7-Pad97)") (class "Default")
      (node (ref "U1") (pin "97") (pinfunction "PC7_97") (pintype "bidirectional"))
    )
    (net (code "116") (name "unconnected-(U1-PC8-Pad98)") (class "Default")
      (node (ref "U1") (pin "98") (pinfunction "PC8_98") (pintype "bidirectional"))
    )
    (net (code "117") (name "unconnected-(U1-PC9-Pad99)") (class "Default")
      (node (ref "U1") (pin "99") (pinfunction "PC9_99") (pintype "bidirectional"))
    )
    (net (code "118") (name "unconnected-(U1-PD0-Pad114)") (class "Default")
      (node (ref "U1") (pin "114") (pinfunction "PD0_114") (pintype "bidirectional"))
    )
    (net (code "119") (name "unconnected-(U1-PD1-Pad115)") (class "Default")
      (node (ref "U1") (pin "115") (pinfunction "PD1_115") (pintype "bidirectional"))
    )
    (net (code "120") (name "unconnected-(U1-PD2-Pad116)") (class "Default")
      (node (ref "U1") (pin "116") (pinfunction "PD2_116") (pintype "bidirectional"))
    )
    (net (code "121") (name "unconnected-(U1-PD3-Pad117)") (class "Default")
      (node (ref "U1") (pin "117") (pinfunction "PD3_117") (pintype "bidirectional"))
    )
    (net (code "122") (name "unconnected-(U1-PD4-Pad118)") (class "Default")
      (node (ref "U1") (pin "118") (pinfunction "PD4_118") (pintype "bidirectional"))
    )
    (net (code "123") (name "unconnected-(U1-PD5-Pad119)") (class "Default")
      (node (ref "U1") (pin "119") (pinfunction "PD5_119") (pintype "bidirectional"))
    )
    (net (code "124") (name "unconnected-(U1-PD6-Pad122)") (class "Default")
      (node (ref "U1") (pin "122") (pinfunction "PD6_122") (pintype "bidirectional"))
    )
    (net (code "125") (name "unconnected-(U1-PD7-Pad123)") (class "Default")
      (node (ref "U1") (pin "123") (pinfunction "PD7_123") (pintype "bidirectional"))
    )
    (net (code "126") (name "unconnected-(U1-PD10-Pad79)") (class "Default")
      (node (ref "U1") (pin "79") (pinfunction "PD10_79") (pintype "bidirectional"))
    )
    (net (code "127") (name "unconnected-(U1-PD11-Pad80)") (class "Default")
      (node (ref "U1") (pin "80") (pinfunction "PD11_80") (pintype "bidirectional"))
    )
    (net (code "128") (name "unconnected-(U1-PD12-Pad81)") (class "Default")
      (node (ref "U1") (pin "81") (pinfunction "PD12_81") (pintype "bidirectional"))
    )
    (net (code "129") (name "unconnected-(U1-PD13-Pad82)") (class "Default")
      (node (ref "U1") (pin "82") (pinfunction "PD13_82") (pintype "bidirectional"))
    )
    (net (code "130") (name "unconnected-(U1-PE2-Pad1)") (class "Default")
      (node (ref "U1") (pin "1") (pinfunction "PE2_1") (pintype "bidirectional"))
    )
    (net (code "131") (name "unconnected-(U1-PE3-Pad2)") (class "Default")
      (node (ref "U1") (pin "2") (pinfunction "PE3_2") (pintype "bidirectional"))
    )
    (net (code "132") (name "unconnected-(U1-PE4-Pad3)") (class "Default")
      (node (ref "U1") (pin "3") (pinfunction "PE4_3") (pintype "bidirectional"))
    )
    (net (code "133") (name "unconnected-(U1-PE5-Pad4)") (class "Default")
      (node (ref "U1") (pin "4") (pinfunction "PE5_4") (pintype "bidirectional"))
    )
    (net (code "134") (name "unconnected-(U1-PE6-Pad5)") (class "Default")
      (node (ref "U1") (pin "5") (pinfunction "PE6_5") (pintype "bidirectional"))
    )
    (net (code "135") (name "unconnected-(U1-PE7-Pad58)") (class "Default")
      (node (ref "U1") (pin "58") (pinfunction "PE7_58") (pintype "bidirectional"))
    )
    (net (code "136") (name "unconnected-(U1-PE8-Pad59)") (class "Default")
      (node (ref "U1") (pin "59") (pinfunction "PE8_59") (pintype "bidirectional"))
    )
    (net (code "137") (name "unconnected-(U1-PE10-Pad63)") (class "Default")
      (node (ref "U1") (pin "63") (pinfunction "PE10_63") (pintype "bidirectional"))
    )
    (net (code "138") (name "unconnected-(U1-PE12-Pad65)") (class "Default")
      (node (ref "U1") (pin "65") (pinfunction "PE12_65") (pintype "bidirectional"))
    )
    (net (code "139") (name "unconnected-(U1-PE14-Pad67)") (class "Default")
      (node (ref "U1") (pin "67") (pinfunction "PE14_67") (pintype "bidirectional"))
    )
    (net (code "140") (name "unconnected-(U1-PF0-Pad10)") (class "Default")
      (node (ref "U1") (pin "10") (pinfunction "PF0_10") (pintype "bidirectional"))
    )
    (net (code "141") (name "unconnected-(U1-PF1-Pad11)") (class "Default")
      (node (ref "U1") (pin "11") (pinfunction "PF1_11") (pintype "bidirectional"))
    )
    (net (code "142") (name "unconnected-(U1-PF2-Pad12)") (class "Default")
      (node (ref "U1") (pin "12") (pinfunction "PF2_12") (pintype "bidirectional"))
    )
    (net (code "143") (name "unconnected-(U1-PF3-Pad13)") (class "Default")
      (node (ref "U1") (pin "13") (pinfunction "PF3_13") (pintype "bidirectional"))
    )
    (net (code "144") (name "unconnected-(U1-PF4-Pad14)") (class "Default")
      (node (ref "U1") (pin "14") (pinfunction "PF4_14") (pintype "bidirectional"))
    )
    (net (code "145") (name "unconnected-(U1-PF5-Pad15)") (class "Default")
      (node (ref "U1") (pin "15") (pinfunction "PF5_15") (pintype "bidirectional"))
    )
    (net (code "146") (name "unconnected-(U1-PF6-Pad18)") (class "Default")
      (node (ref "U1") (pin "18") (pinfunction "PF6_18") (pintype "bidirectional"))
    )
    (net (code "147") (name "unconnected-(U1-PF7-Pad19)") (class "Default")
      (node (ref "U1") (pin "19") (pinfunction "PF7_19") (pintype "bidirectional"))
    )
    (net (code "148") (name "unconnected-(U1-PF8-Pad20)") (class "Default")
      (node (ref "U1") (pin "20") (pinfunction "PF8_20") (pintype "bidirectional"))
    )
    (net (code "149") (name "unconnected-(U1-PF9-Pad21)") (class "Default")
      (node (ref "U1") (pin "21") (pinfunction "PF9_21") (pintype "bidirectional"))
    )
    (net (code "150") (name "unconnected-(U1-PF10-Pad22)") (class "Default")
      (node (ref "U1") (pin "22") (pinfunction "PF10_22") (pintype "bidirectional"))
    )
    (net (code "151") (name "unconnected-(U1-PF11-Pad49)") (class "Default")
      (node (ref "U1") (pin "49") (pinfunction "PF11_49") (pintype "bidirectional"))
    )
    (net (code "152") (name "unconnected-(U1-PG0-Pad56)") (class "Default")
      (node (ref "U1") (pin "56") (pinfunction "PG0_56") (pintype "bidirectional"))
    )
    (net (code "153") (name "unconnected-(U1-PG1-Pad57)") (class "Default")
      (node (ref "U1") (pin "57") (pinfunction "PG1_57") (pintype "bidirectional"))
    )
    (net (code "154") (name "unconnected-(U1-PG2-Pad87)") (class "Default")
      (node (ref "U1") (pin "87") (pinfunction "PG2_87") (pintype "bidirectional"))
    )
    (net (code "155") (name "unconnected-(U1-PG3-Pad88)") (class "Default")
      (node (ref "U1") (pin "88") (pinfunction "PG3_88") (pintype "bidirectional"))
    )
    (net (code "156") (name "unconnected-(U1-PG4-Pad89)") (class "Default")
      (node (ref "U1") (pin "89") (pinfunction "PG4_89") (pintype "bidirectional"))
    )
    (net (code "157") (name "unconnected-(U1-PG5-Pad90)") (class "Default")
      (node (ref "U1") (pin "90") (pinfunction "PG5_90") (pintype "bidirectional"))
    )
    (net (code "158") (name "unconnected-(U1-PG6-Pad91)") (class "Default")
      (node (ref "U1") (pin "91") (pinfunction "PG6_91") (pintype "bidirectional"))
    )
    (net (code "159") (name "unconnected-(U1-PG7-Pad92)") (class "Default")
      (node (ref "U1") (pin "92") (pinfunction "PG7_92") (pintype "bidirectional"))
    )
    (net (code "160") (name "unconnected-(U1-PG8-Pad93)") (class "Default")
      (node (ref "U1") (pin "93") (pinfunction "PG8_93") (pintype "bidirectional"))
    )
    (net (code "161") (name "unconnected-(U1-PG10-Pad125)") (class "Default")
      (node (ref "U1") (pin "125") (pinfunction "PG10_125") (pintype "bidirectional"))
    )
    (net (code "162") (name "unconnected-(U1-PG11-Pad126)") (class "Default")
      (node (ref "U1") (pin "126") (pinfunction "PG11_126") (pintype "bidirectional"))
    )
    (net (code "163") (name "unconnected-(U1-PG12-Pad127)") (class "Default")
      (node (ref "U1") (pin "127") (pinfunction "PG12_127") (pintype "bidirectional"))
    )
    (net (code "164") (name "unconnected-(U1-PG13-Pad128)") (class "Default")
      (node (ref "U1") (pin "128") (pinfunction "PG13_128") (pintype "bidirectional"))
    )
    (net (code "165") (name "unconnected-(U1-PG15-Pad132)") (class "Default")
      (node (ref "U1") (pin "132") (pinfunction "PG15_132") (pintype "bidirectional"))
    )
    (net (code "166") (name "unconnected-(U2-NC-Pad5)") (class "Default")
      (node (ref "U2") (pin "5") (pinfunction "NC_5") (pintype "no_connect"))
    )
    (net (code "167") (name "unconnected-(U2-PG-Pad3)") (class "Default")
      (node (ref "U2") (pin "3") (pinfunction "PG_3") (pintype "bidirectional"))
    )
    (net (code "168") (name "unconnected-(U3-O.S.-Pad3)") (class "Default")
      (node (ref "U3") (pin "3") (pinfunction "O.S._3") (pintype "bidirectional"))
    )
    (net (code "169") (name "unconnected-(U5-NC-Pad4)") (class "Default")
      (node (ref "U5") (pin "4") (pinfunction "NC_4") (pintype "no_connect"))
    )
    (net (code "170") (name "unconnected-(U7-A0-Pad2)") (class "Default")
      (node (ref "U7") (pin "2") (pinfunction "A0_2") (pintype "bidirectional"))
    )
    (net (code "171") (name "unconnected-(U7-A2-Pad4)") (class "Default")
      (node (ref "U7") (pin "4") (pinfunction "A2_4") (pintype "bidirectional"))
    )
    (net (code "172") (name "unconnected-(U7-A4-Pad6)") (class "Default")
      (node (ref "U7") (pin "6") (pinfunction "A4_6") (pintype "bidirectional"))
    )
    (net (code "173") (name "unconnected-(U7-A6-Pad8)") (class "Default")
      (node (ref "U7") (pin "8") (pinfunction "A6_8") (pintype "bidirectional"))
    )
    (net (code "174") (name "unconnected-(U7-B0-Pad19)") (class "Default")
      (node (ref "U7") (pin "19") (pinfunction "B0_19") (pintype "bidirectional"))
    )
    (net (code "175") (name "unconnected-(U7-B2-Pad17)") (class "Default")
      (node (ref "U7") (pin "17") (pinfunction "B2_17") (pintype "bidirectional"))
    )
    (net (code "176") (name "unconnected-(U7-B4-Pad15)") (class "Default")
      (node (ref "U7") (pin "15") (pinfunction "B4_15") (pintype "bidirectional"))
    )
    (net (code "177") (name "unconnected-(U7-B6-Pad13)") (class "Default")
      (node (ref "U7") (pin "13") (pinfunction "B6_13") (pintype "bidirectional"))
    )
    (net (code "178") (name "unconnected-(U7-DAP-Pad0)") (class "Default")
      (node (ref "U7") (pin "0") (pinfunction "DAP_0") (pintype "no_connect"))
    )
    (net (code "179") (name "unconnected-(U9-NC-Pad3)") (class "Default")
      (node (ref "U9") (pin "3") (pinfunction "NC_3") (pintype "no_connect"))
    )
    (net (code "180") (name "unconnected-(U9-NC2-Pad6)") (class "Default")
      (node (ref "U9") (pin "6") (pinfunction "NC2_6") (pintype "no_connect"))
    )
    (net (code "181") (name "unconnected-(U9-NC3-Pad8)") (class "Default")
      (node (ref "U9") (pin "8") (pinfunction "NC3_8") (pintype "no_connect"))
    )
    (net (code "182") (name "~{CS}") (class "Default")
      (node (ref "U6") (pin "1") (pinfunction "~{CS}_1") (pintype "bidirectional"))
      (node (ref "U7") (pin "3") (pinfunction "A1_3") (pintype "bidirectional"))
    )
    (net (code "183") (name "~{OE}") (class "Default")
      (node (ref "R5") (pin "2") (pinfunction "2_2") (pintype "passive"))
      (node (ref "U7") (pin "11") (pinfunction "~{OE}_11") (pintype "passive"))
    )
  )
)
